# IQModulator.net
KiCad netlist of a schematic drawn in EAGLE
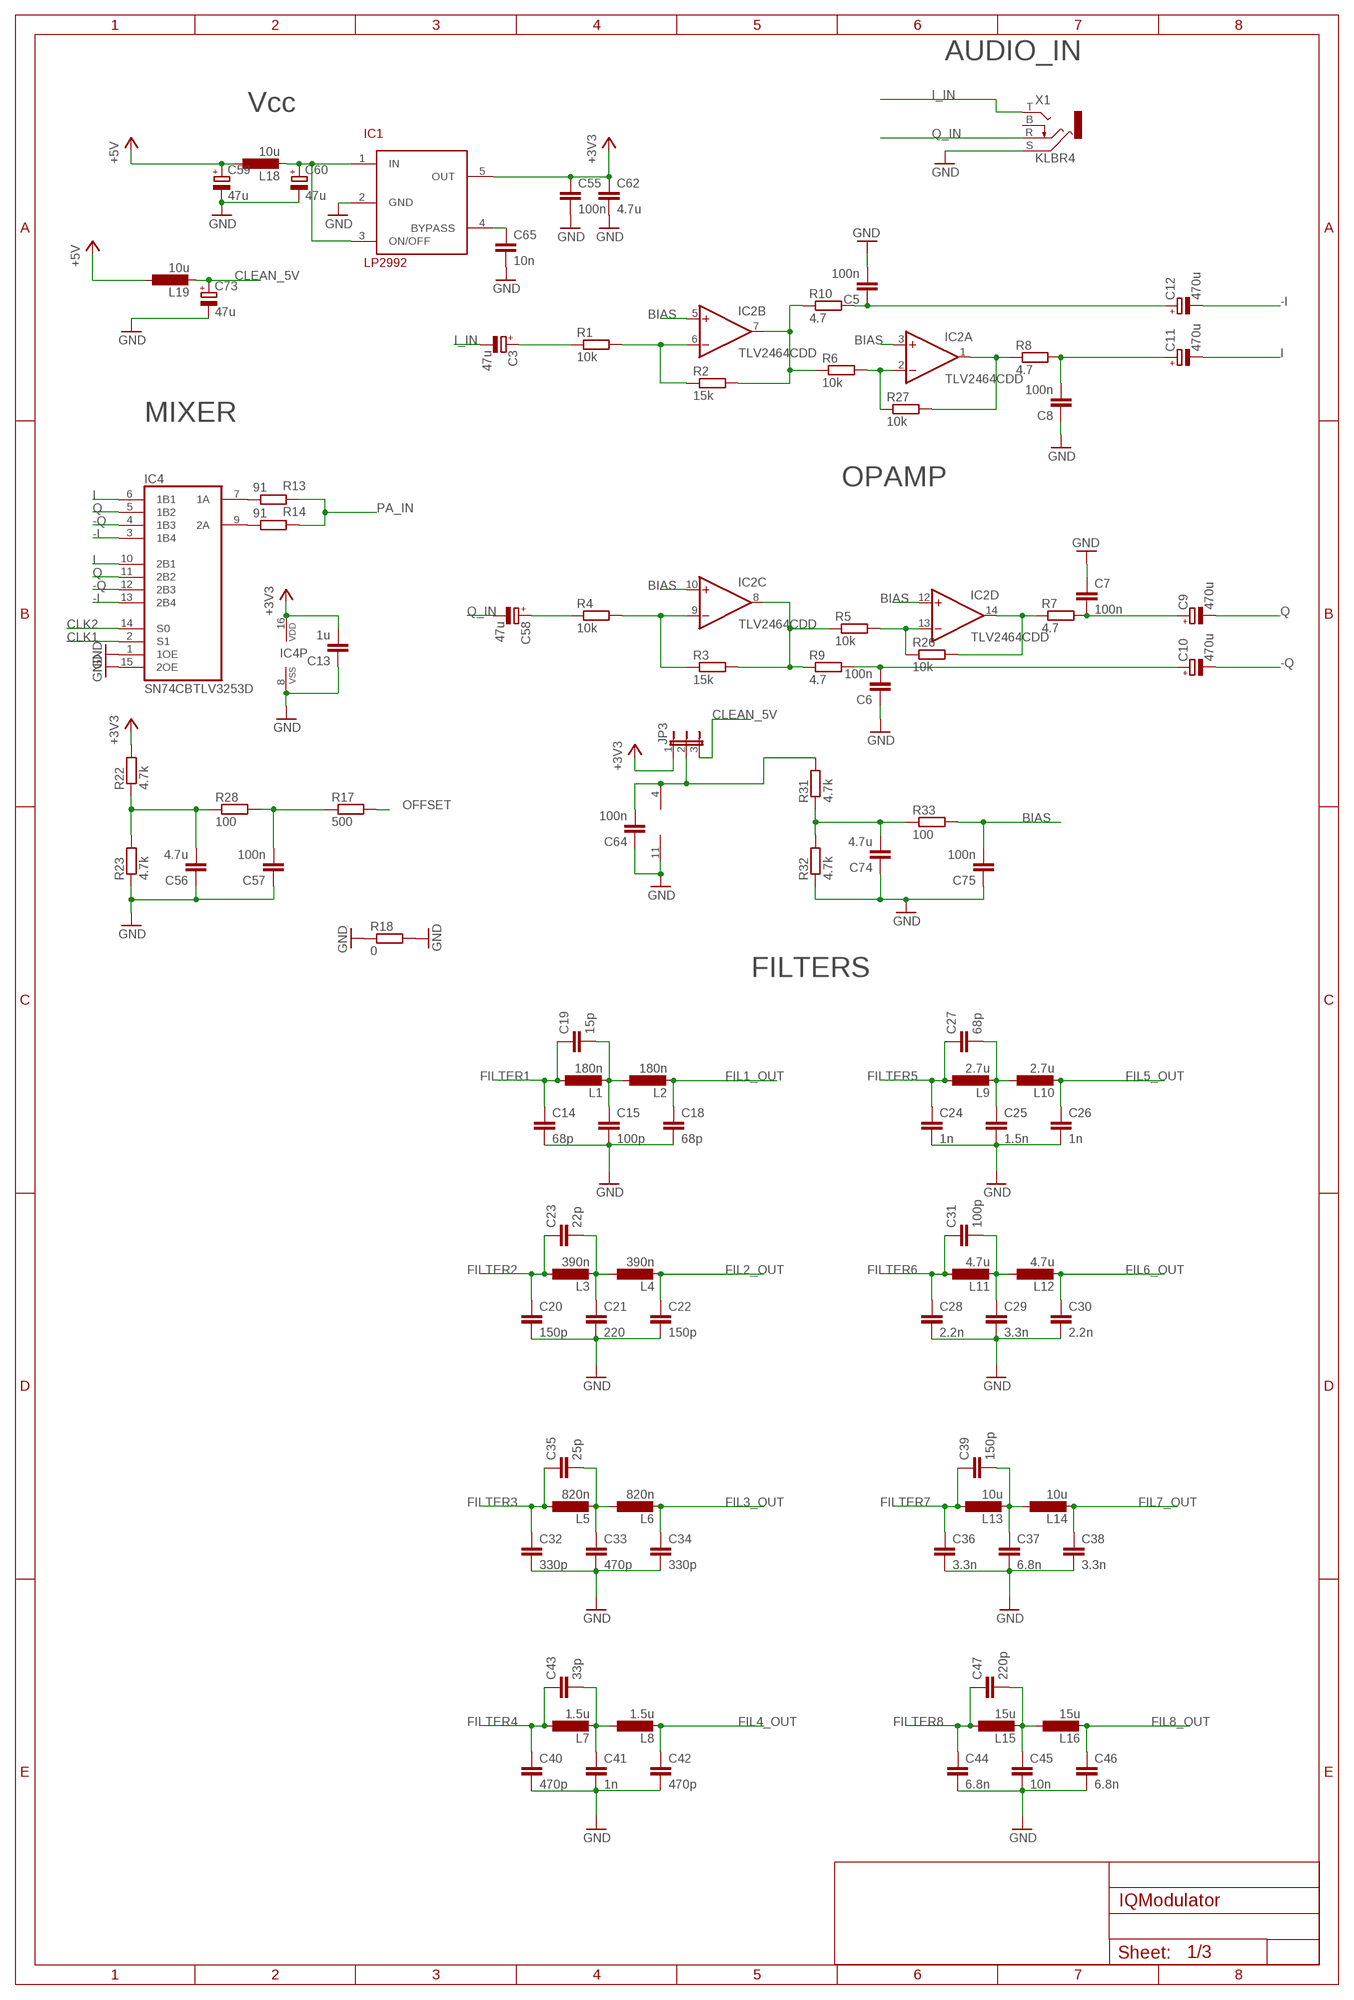
[diagram p0: schematic, sheet 1]
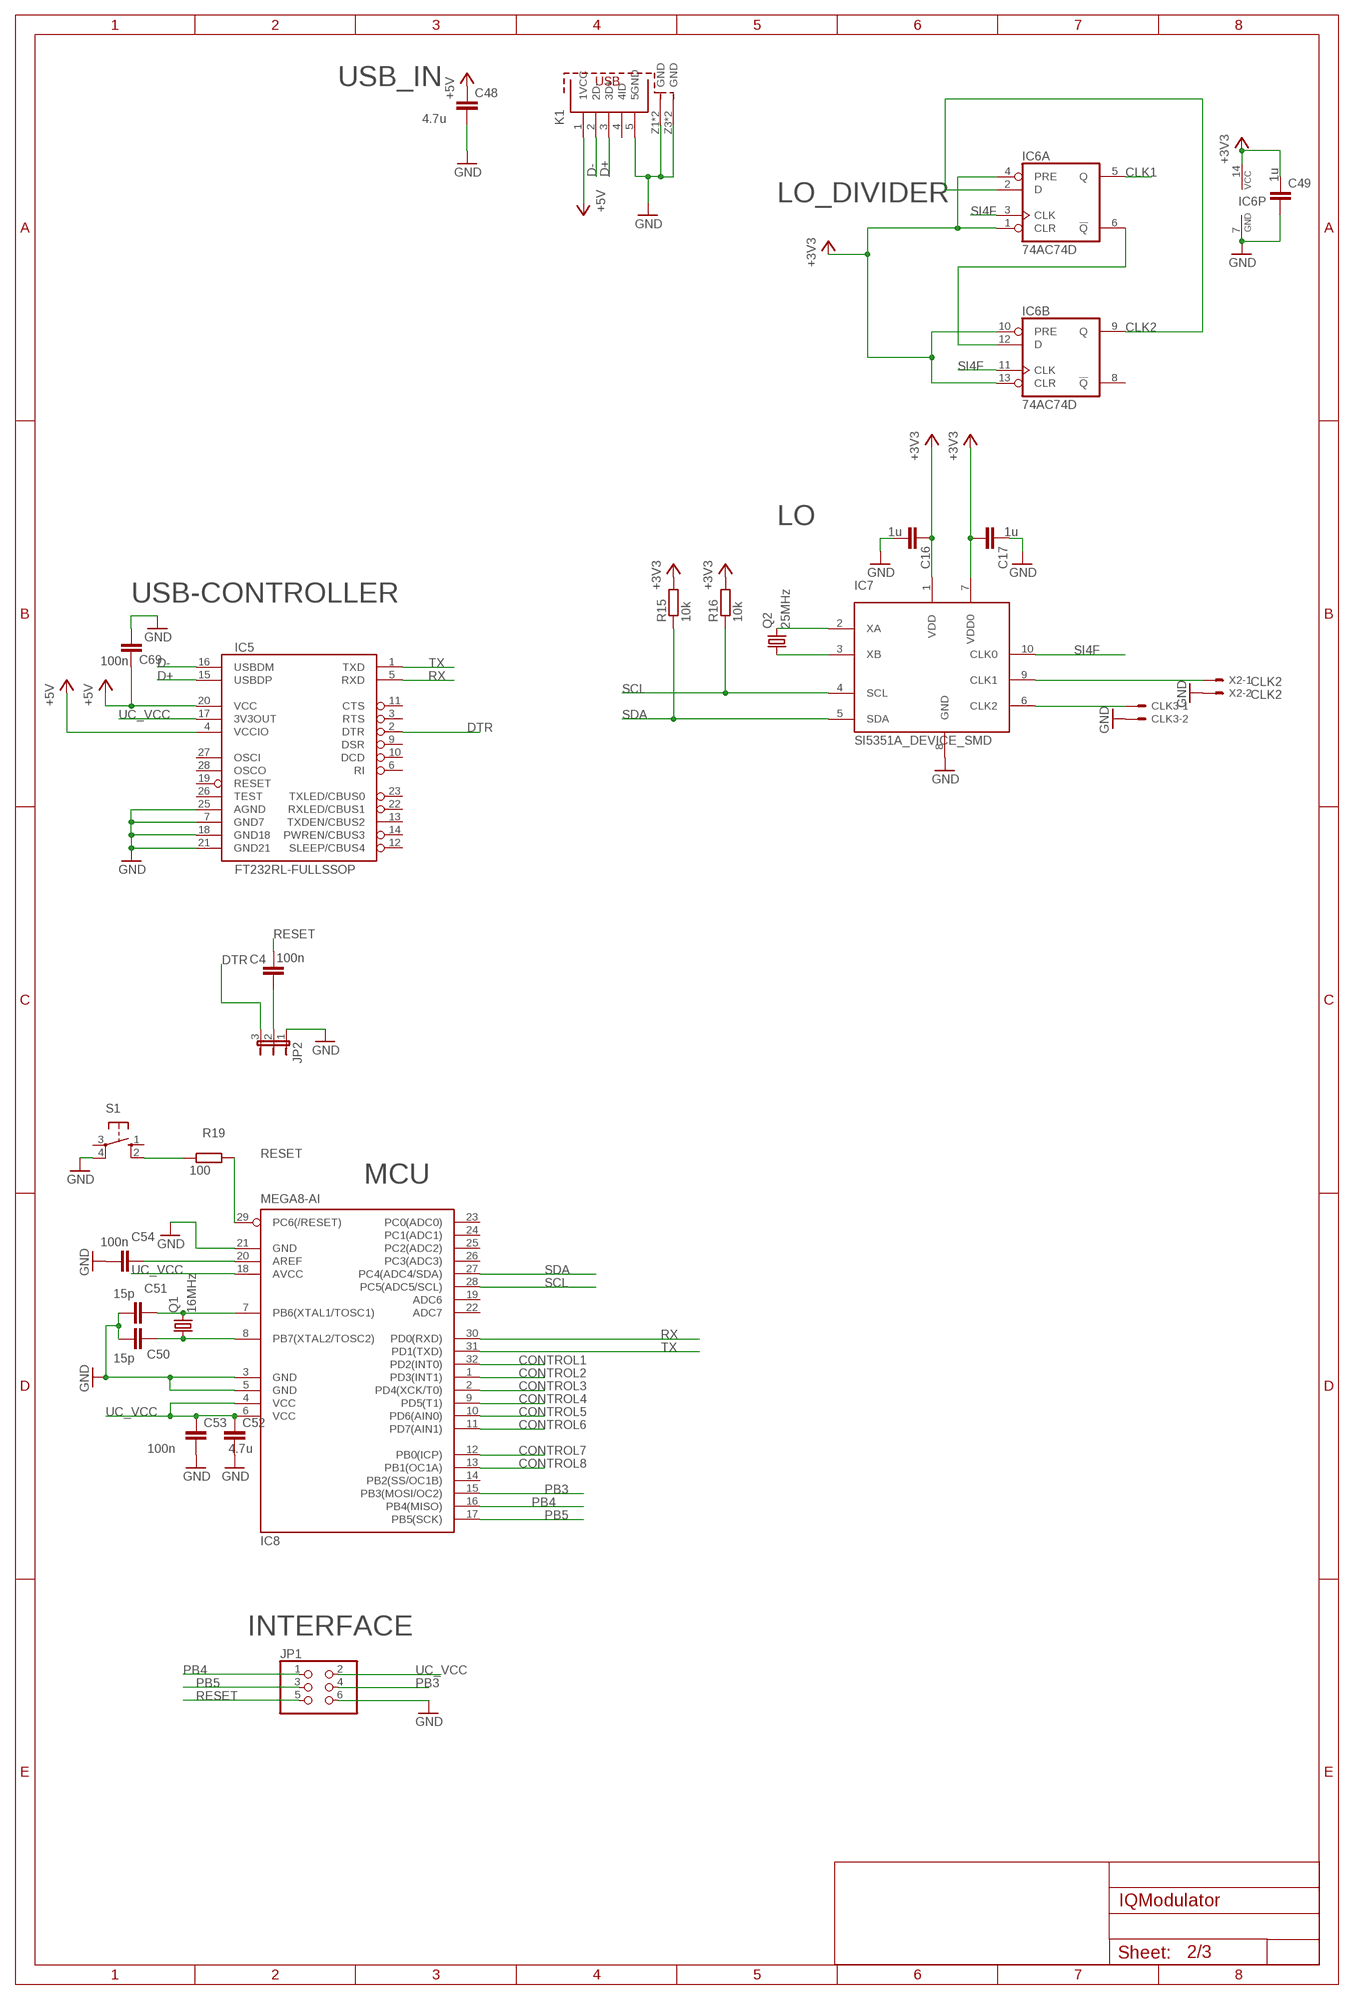
[diagram p1: schematic, sheet 2]
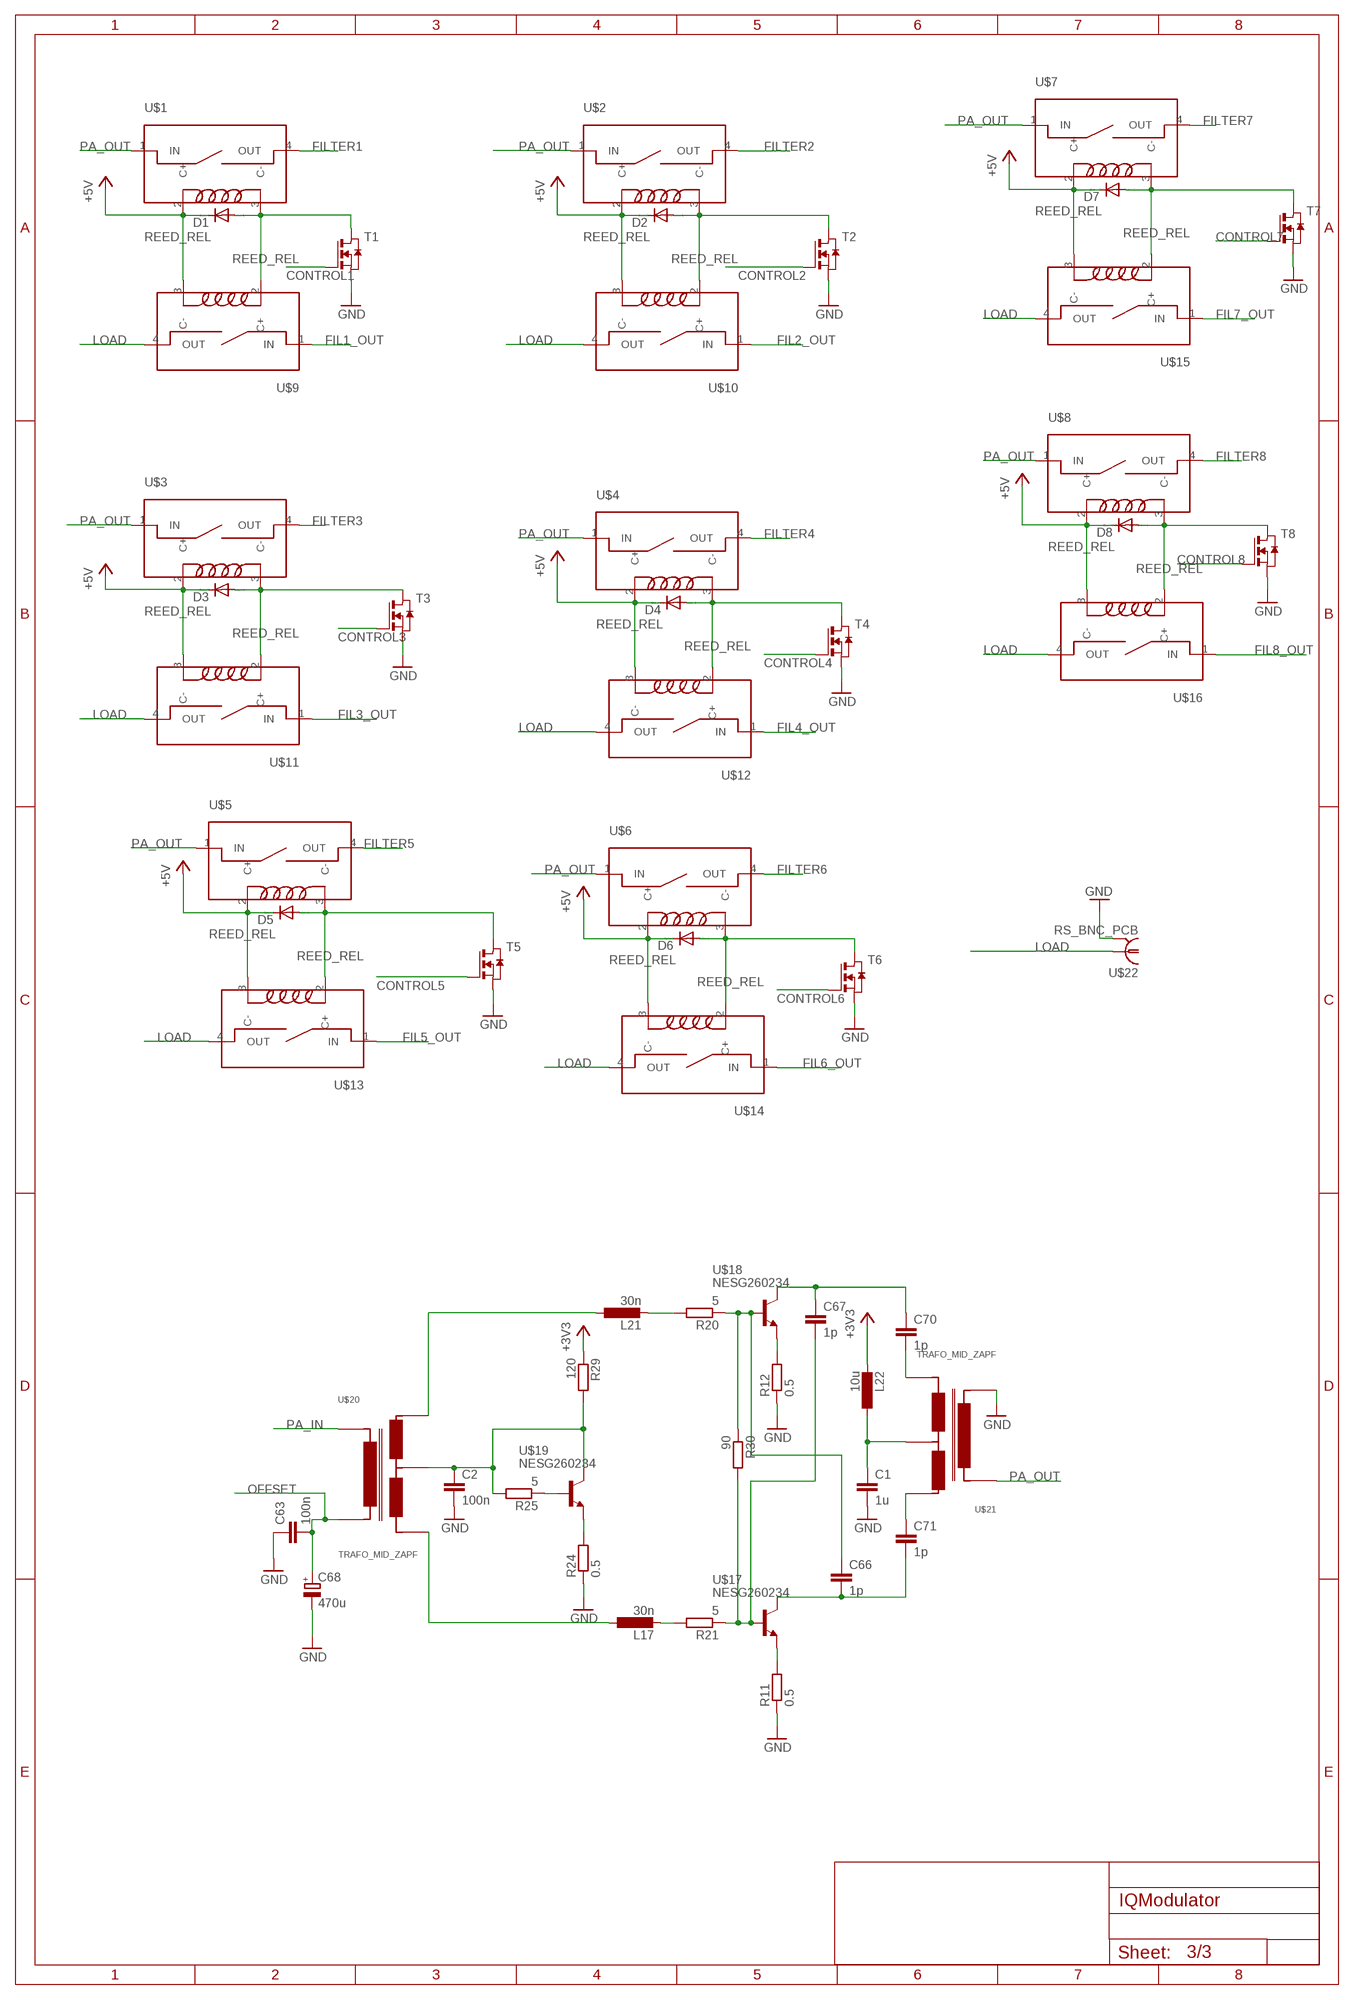
[diagram p2: schematic, sheet 3]

(export (version "E")
  (design (tool "Eeschema 10.0.6"))
  (components
    (comp (ref "C3")
      (value "47u")
      (footprint "eagle-import:PANASONIC_C")
      (libsource (lib "eagle-import") (part "CPOL-EUC"))
    )
    (comp (ref "C5")
      (value "100n")
      (footprint "eagle-import:C0805")
      (libsource (lib "eagle-import") (part "resistor_C-EUC0805"))
    )
    (comp (ref "C6")
      (value "100n")
      (footprint "eagle-import:C0805")
      (libsource (lib "eagle-import") (part "resistor_C-EUC0805"))
    )
    (comp (ref "C7")
      (value "100n")
      (footprint "eagle-import:C0805")
      (libsource (lib "eagle-import") (part "resistor_C-EUC0805"))
    )
    (comp (ref "C8")
      (value "100n")
      (footprint "eagle-import:C0805")
      (libsource (lib "eagle-import") (part "resistor_C-EUC0805"))
    )
    (comp (ref "C9")
      (value "470u")
      (footprint "eagle-import:PANASONIC_D")
      (libsource (lib "eagle-import") (part "CPOL-EUD"))
    )
    (comp (ref "C10")
      (value "470u")
      (footprint "eagle-import:PANASONIC_D")
      (libsource (lib "eagle-import") (part "CPOL-EUD"))
    )
    (comp (ref "C11")
      (value "470u")
      (footprint "eagle-import:PANASONIC_D")
      (libsource (lib "eagle-import") (part "CPOL-EUD"))
    )
    (comp (ref "C12")
      (value "470u")
      (footprint "eagle-import:PANASONIC_D")
      (libsource (lib "eagle-import") (part "CPOL-EUD"))
    )
    (comp (ref "C13")
      (value "1u")
      (footprint "eagle-import:C0805")
      (libsource (lib "eagle-import") (part "resistor_C-EUC0805"))
    )
    (comp (ref "C14")
      (value "68p")
      (footprint "eagle-import:C0805")
      (libsource (lib "eagle-import") (part "resistor_C-EUC0805"))
    )
    (comp (ref "C15")
      (value "100p")
      (footprint "eagle-import:C0805")
      (libsource (lib "eagle-import") (part "resistor_C-EUC0805"))
    )
    (comp (ref "C18")
      (value "68p")
      (footprint "eagle-import:C0805")
      (libsource (lib "eagle-import") (part "resistor_C-EUC0805"))
    )
    (comp (ref "C19")
      (value "15p")
      (footprint "eagle-import:C0805")
      (libsource (lib "eagle-import") (part "resistor_C-EUC0805"))
    )
    (comp (ref "C20")
      (value "150p")
      (footprint "eagle-import:C0805")
      (libsource (lib "eagle-import") (part "resistor_C-EUC0805"))
    )
    (comp (ref "C21")
      (value "220")
      (footprint "eagle-import:C0805")
      (libsource (lib "eagle-import") (part "resistor_C-EUC0805"))
    )
    (comp (ref "C22")
      (value "150p")
      (footprint "eagle-import:C0805")
      (libsource (lib "eagle-import") (part "resistor_C-EUC0805"))
    )
    (comp (ref "C23")
      (value "22p")
      (footprint "eagle-import:C0805")
      (libsource (lib "eagle-import") (part "resistor_C-EUC0805"))
    )
    (comp (ref "C24")
      (value "1n")
      (footprint "eagle-import:C0805")
      (libsource (lib "eagle-import") (part "resistor_C-EUC0805"))
    )
    (comp (ref "C25")
      (value "1.5n")
      (footprint "eagle-import:C0805")
      (libsource (lib "eagle-import") (part "resistor_C-EUC0805"))
    )
    (comp (ref "C26")
      (value "1n")
      (footprint "eagle-import:C0805")
      (libsource (lib "eagle-import") (part "resistor_C-EUC0805"))
    )
    (comp (ref "C27")
      (value "68p")
      (footprint "eagle-import:C0805")
      (libsource (lib "eagle-import") (part "resistor_C-EUC0805"))
    )
    (comp (ref "C28")
      (value "2.2n")
      (footprint "eagle-import:C0805")
      (libsource (lib "eagle-import") (part "resistor_C-EUC0805"))
    )
    (comp (ref "C29")
      (value "3.3n")
      (footprint "eagle-import:C0805")
      (libsource (lib "eagle-import") (part "resistor_C-EUC0805"))
    )
    (comp (ref "C30")
      (value "2.2n")
      (footprint "eagle-import:C0805")
      (libsource (lib "eagle-import") (part "resistor_C-EUC0805"))
    )
    (comp (ref "C31")
      (value "100p")
      (footprint "eagle-import:C0805")
      (libsource (lib "eagle-import") (part "resistor_C-EUC0805"))
    )
    (comp (ref "C32")
      (value "330p")
      (footprint "eagle-import:C0805")
      (libsource (lib "eagle-import") (part "resistor_C-EUC0805"))
    )
    (comp (ref "C33")
      (value "470p")
      (footprint "eagle-import:C0805")
      (libsource (lib "eagle-import") (part "resistor_C-EUC0805"))
    )
    (comp (ref "C34")
      (value "330p")
      (footprint "eagle-import:C0805")
      (libsource (lib "eagle-import") (part "resistor_C-EUC0805"))
    )
    (comp (ref "C35")
      (value "25p")
      (footprint "eagle-import:C0805")
      (libsource (lib "eagle-import") (part "resistor_C-EUC0805"))
    )
    (comp (ref "C36")
      (value "3.3n")
      (footprint "eagle-import:C0805")
      (libsource (lib "eagle-import") (part "resistor_C-EUC0805"))
    )
    (comp (ref "C37")
      (value "6.8n")
      (footprint "eagle-import:C0805")
      (libsource (lib "eagle-import") (part "resistor_C-EUC0805"))
    )
    (comp (ref "C38")
      (value "3.3n")
      (footprint "eagle-import:C0805")
      (libsource (lib "eagle-import") (part "resistor_C-EUC0805"))
    )
    (comp (ref "C39")
      (value "150p")
      (footprint "eagle-import:C0805")
      (libsource (lib "eagle-import") (part "resistor_C-EUC0805"))
    )
    (comp (ref "C40")
      (value "470p")
      (footprint "eagle-import:C0805")
      (libsource (lib "eagle-import") (part "resistor_C-EUC0805"))
    )
    (comp (ref "C41")
      (value "1n")
      (footprint "eagle-import:C0805")
      (libsource (lib "eagle-import") (part "resistor_C-EUC0805"))
    )
    (comp (ref "C42")
      (value "470p")
      (footprint "eagle-import:C0805")
      (libsource (lib "eagle-import") (part "resistor_C-EUC0805"))
    )
    (comp (ref "C43")
      (value "33p")
      (footprint "eagle-import:C0805")
      (libsource (lib "eagle-import") (part "resistor_C-EUC0805"))
    )
    (comp (ref "C44")
      (value "6.8n")
      (footprint "eagle-import:C0805")
      (libsource (lib "eagle-import") (part "resistor_C-EUC0805"))
    )
    (comp (ref "C45")
      (value "10n")
      (footprint "eagle-import:C0805")
      (libsource (lib "eagle-import") (part "resistor_C-EUC0805"))
    )
    (comp (ref "C46")
      (value "6.8n")
      (footprint "eagle-import:C0805")
      (libsource (lib "eagle-import") (part "resistor_C-EUC0805"))
    )
    (comp (ref "C47")
      (value "220p")
      (footprint "eagle-import:C0805")
      (libsource (lib "eagle-import") (part "resistor_C-EUC0805"))
    )
    (comp (ref "C55")
      (value "100n")
      (footprint "eagle-import:C0805")
      (libsource (lib "eagle-import") (part "resistor_C-EUC0805"))
    )
    (comp (ref "C56")
      (value "4.7u")
      (footprint "eagle-import:C0805")
      (libsource (lib "eagle-import") (part "resistor_C-EUC0805"))
    )
    (comp (ref "C57")
      (value "100n")
      (footprint "eagle-import:C0805")
      (libsource (lib "eagle-import") (part "resistor_C-EUC0805"))
    )
    (comp (ref "C58")
      (value "47u")
      (footprint "eagle-import:PANASONIC_C")
      (libsource (lib "eagle-import") (part "CPOL-EUC"))
    )
    (comp (ref "C59")
      (value "47u")
      (footprint "eagle-import:PANASONIC_C")
      (libsource (lib "eagle-import") (part "CPOL-EUC"))
    )
    (comp (ref "C60")
      (value "47u")
      (footprint "eagle-import:PANASONIC_C")
      (libsource (lib "eagle-import") (part "CPOL-EUC"))
    )
    (comp (ref "C62")
      (value "4.7u")
      (footprint "eagle-import:C0805")
      (libsource (lib "eagle-import") (part "resistor_C-EUC0805"))
    )
    (comp (ref "C64")
      (value "100n")
      (footprint "eagle-import:C0805")
      (libsource (lib "eagle-import") (part "resistor_C-EUC0805"))
    )
    (comp (ref "C65")
      (value "10n")
      (footprint "eagle-import:C0805")
      (libsource (lib "eagle-import") (part "resistor_C-EUC0805"))
    )
    (comp (ref "C73")
      (value "47u")
      (footprint "eagle-import:PANASONIC_C")
      (libsource (lib "eagle-import") (part "CPOL-EUC"))
    )
    (comp (ref "C74")
      (value "4.7u")
      (footprint "eagle-import:C0805")
      (libsource (lib "eagle-import") (part "resistor_C-EUC0805"))
    )
    (comp (ref "C75")
      (value "100n")
      (footprint "eagle-import:C0805")
      (libsource (lib "eagle-import") (part "resistor_C-EUC0805"))
    )
    (comp (ref "IC1")
      (value "LP2992")
      (footprint "eagle-import:SOT-23-5")
      (libsource (lib "eagle-import") (part "LP2992"))
    )
    (comp (ref "IC2")
      (value "TLV2464CDD")
      (footprint "eagle-import:SO14")
      (libsource (lib "eagle-import") (part "TLV2464CDD"))
    )
    (comp (ref "IC4")
      (value "SN74CBTLV3253D")
      (footprint "eagle-import:SO16")
      (libsource (lib "eagle-import") (part "SN74CBTLV3253D"))
    )
    (comp (ref "JP3")
      (value "JP2E")
      (footprint "eagle-import:JP2")
      (libsource (lib "eagle-import") (part "JP2E"))
    )
    (comp (ref "L1")
      (value "180n")
      (footprint "eagle-import:L0805")
      (libsource (lib "eagle-import") (part "LL0805"))
    )
    (comp (ref "L2")
      (value "180n")
      (footprint "eagle-import:L0805")
      (libsource (lib "eagle-import") (part "LL0805"))
    )
    (comp (ref "L3")
      (value "390n")
      (footprint "eagle-import:L0805")
      (libsource (lib "eagle-import") (part "LL0805"))
    )
    (comp (ref "L4")
      (value "390n")
      (footprint "eagle-import:L0805")
      (libsource (lib "eagle-import") (part "LL0805"))
    )
    (comp (ref "L5")
      (value "820n")
      (footprint "eagle-import:L0805")
      (libsource (lib "eagle-import") (part "LL0805"))
    )
    (comp (ref "L6")
      (value "820n")
      (footprint "eagle-import:L0805")
      (libsource (lib "eagle-import") (part "LL0805"))
    )
    (comp (ref "L7")
      (value "1.5u")
      (footprint "eagle-import:L0805")
      (libsource (lib "eagle-import") (part "LL0805"))
    )
    (comp (ref "L8")
      (value "1.5u")
      (footprint "eagle-import:L0805")
      (libsource (lib "eagle-import") (part "LL0805"))
    )
    (comp (ref "L9")
      (value "2.7u")
      (footprint "eagle-import:L0805")
      (libsource (lib "eagle-import") (part "LL0805"))
    )
    (comp (ref "L10")
      (value "2.7u")
      (footprint "eagle-import:L0805")
      (libsource (lib "eagle-import") (part "LL0805"))
    )
    (comp (ref "L11")
      (value "4.7u")
      (footprint "eagle-import:L0805")
      (libsource (lib "eagle-import") (part "LL0805"))
    )
    (comp (ref "L12")
      (value "4.7u")
      (footprint "eagle-import:L0805")
      (libsource (lib "eagle-import") (part "LL0805"))
    )
    (comp (ref "L13")
      (value "10u")
      (footprint "eagle-import:L0805")
      (libsource (lib "eagle-import") (part "LL0805"))
    )
    (comp (ref "L14")
      (value "10u")
      (footprint "eagle-import:L0805")
      (libsource (lib "eagle-import") (part "LL0805"))
    )
    (comp (ref "L15")
      (value "15u")
      (footprint "eagle-import:L1008")
      (libsource (lib "eagle-import") (part "L1008"))
    )
    (comp (ref "L16")
      (value "15u")
      (footprint "eagle-import:L1008")
      (libsource (lib "eagle-import") (part "L1008"))
    )
    (comp (ref "L18")
      (value "10u")
      (footprint "eagle-import:L1008")
      (libsource (lib "eagle-import") (part "L1008"))
    )
    (comp (ref "L19")
      (value "10u")
      (footprint "eagle-import:L1008")
      (libsource (lib "eagle-import") (part "L1008"))
    )
    (comp (ref "R1")
      (value "10k")
      (footprint "eagle-import:R0805")
      (libsource (lib "eagle-import") (part "resistor_R-EU_R0805"))
    )
    (comp (ref "R2")
      (value "15k")
      (footprint "eagle-import:R0805")
      (libsource (lib "eagle-import") (part "resistor_R-EU_R0805"))
    )
    (comp (ref "R3")
      (value "15k")
      (footprint "eagle-import:R0805")
      (libsource (lib "eagle-import") (part "resistor_R-EU_R0805"))
    )
    (comp (ref "R4")
      (value "10k")
      (footprint "eagle-import:R0805")
      (libsource (lib "eagle-import") (part "resistor_R-EU_R0805"))
    )
    (comp (ref "R5")
      (value "10k")
      (footprint "eagle-import:R0805")
      (libsource (lib "eagle-import") (part "resistor_R-EU_R0805"))
    )
    (comp (ref "R6")
      (value "10k")
      (footprint "eagle-import:R0805")
      (libsource (lib "eagle-import") (part "resistor_R-EU_R0805"))
    )
    (comp (ref "R7")
      (value "4.7")
      (footprint "eagle-import:R0805")
      (libsource (lib "eagle-import") (part "resistor_R-EU_R0805"))
    )
    (comp (ref "R8")
      (value "4.7")
      (footprint "eagle-import:R0805")
      (libsource (lib "eagle-import") (part "resistor_R-EU_R0805"))
    )
    (comp (ref "R9")
      (value "4.7")
      (footprint "eagle-import:R0805")
      (libsource (lib "eagle-import") (part "resistor_R-EU_R0805"))
    )
    (comp (ref "R10")
      (value "4.7")
      (footprint "eagle-import:R0805")
      (libsource (lib "eagle-import") (part "resistor_R-EU_R0805"))
    )
    (comp (ref "R13")
      (value "91")
      (footprint "eagle-import:R0805")
      (libsource (lib "eagle-import") (part "resistor_R-EU_R0805"))
    )
    (comp (ref "R14")
      (value "91")
      (footprint "eagle-import:R0805")
      (libsource (lib "eagle-import") (part "resistor_R-EU_R0805"))
    )
    (comp (ref "R17")
      (value "500")
      (footprint "eagle-import:R0805")
      (libsource (lib "eagle-import") (part "resistor_R-EU_R0805"))
    )
    (comp (ref "R18")
      (value "0")
      (footprint "eagle-import:R0805")
      (libsource (lib "eagle-import") (part "resistor_R-EU_R0805"))
    )
    (comp (ref "R22")
      (value "4.7k")
      (footprint "eagle-import:R0805")
      (libsource (lib "eagle-import") (part "resistor_R-EU_R0805"))
    )
    (comp (ref "R23")
      (value "4.7k")
      (footprint "eagle-import:R0805")
      (libsource (lib "eagle-import") (part "resistor_R-EU_R0805"))
    )
    (comp (ref "R26")
      (value "10k")
      (footprint "eagle-import:R0805")
      (libsource (lib "eagle-import") (part "resistor_R-EU_R0805"))
    )
    (comp (ref "R27")
      (value "10k")
      (footprint "eagle-import:R0805")
      (libsource (lib "eagle-import") (part "resistor_R-EU_R0805"))
    )
    (comp (ref "R28")
      (value "100")
      (footprint "eagle-import:R0805")
      (libsource (lib "eagle-import") (part "resistor_R-EU_R0805"))
    )
    (comp (ref "R31")
      (value "4.7k")
      (footprint "eagle-import:R0805")
      (libsource (lib "eagle-import") (part "resistor_R-EU_R0805"))
    )
    (comp (ref "R32")
      (value "4.7k")
      (footprint "eagle-import:R0805")
      (libsource (lib "eagle-import") (part "resistor_R-EU_R0805"))
    )
    (comp (ref "R33")
      (value "100")
      (footprint "eagle-import:R0805")
      (libsource (lib "eagle-import") (part "resistor_R-EU_R0805"))
    )
    (comp (ref "X1")
      (value "KLBR4")
      (footprint "eagle-import:KLBR4")
      (fields (field (name "MPN") "KLBR 4"))
      (libsource (lib "eagle-import") (part "KLBR4"))
    )
    (comp (ref "C4")
      (value "100n")
      (footprint "eagle-import:C0805")
      (libsource (lib "eagle-import") (part "resistor_C-EUC0805"))
    )
    (comp (ref "C16")
      (value "1u")
      (footprint "eagle-import:C0805")
      (libsource (lib "eagle-import") (part "resistor_C-EUC0805"))
    )
    (comp (ref "C17")
      (value "1u")
      (footprint "eagle-import:C0805")
      (libsource (lib "eagle-import") (part "resistor_C-EUC0805"))
    )
    (comp (ref "C48")
      (value "4.7u")
      (footprint "eagle-import:C0805")
      (libsource (lib "eagle-import") (part "resistor_C-EUC0805"))
    )
    (comp (ref "C49")
      (value "1u")
      (footprint "eagle-import:C0805")
      (libsource (lib "eagle-import") (part "resistor_C-EUC0805"))
    )
    (comp (ref "C50")
      (value "15p")
      (footprint "eagle-import:C0805")
      (libsource (lib "eagle-import") (part "resistor_C-EUC0805"))
    )
    (comp (ref "C51")
      (value "15p")
      (footprint "eagle-import:C0805")
      (libsource (lib "eagle-import") (part "resistor_C-EUC0805"))
    )
    (comp (ref "C52")
      (value "4.7u")
      (footprint "eagle-import:C0805")
      (libsource (lib "eagle-import") (part "resistor_C-EUC0805"))
    )
    (comp (ref "C53")
      (value "100n")
      (footprint "eagle-import:C0805")
      (libsource (lib "eagle-import") (part "resistor_C-EUC0805"))
    )
    (comp (ref "C54")
      (value "100n")
      (footprint "eagle-import:C0805")
      (libsource (lib "eagle-import") (part "resistor_C-EUC0805"))
    )
    (comp (ref "C69")
      (value "100n")
      (footprint "eagle-import:C0805")
      (libsource (lib "eagle-import") (part "resistor_C-EUC0805"))
    )
    (comp (ref "CLK3")
      (value "KK-156-2")
      (footprint "eagle-import:KK-156-2")
      (libsource (lib "eagle-import") (part "KK-156-2"))
    )
    (comp (ref "IC5")
      (value "FT232RL-FULLSSOP")
      (footprint "eagle-import:SSOP28DB")
      (libsource (lib "eagle-import") (part "FT232RL-FULLSSOP"))
    )
    (comp (ref "IC6")
      (value "74AC74D")
      (footprint "eagle-import:SO14")
      (libsource (lib "eagle-import") (part "7474DAC"))
    )
    (comp (ref "IC7")
      (value "SI5351A_DEVICE_SMD")
      (footprint "eagle-import:10-MSOP")
      (libsource (lib "eagle-import") (part "SI5351A_DEVICE_SMD"))
    )
    (comp (ref "IC8")
      (value "MEGA8-AI")
      (footprint "eagle-import:TQFP32-08")
      (fields (field (name "MPN") "ATMEGA8-16AU"))
      (libsource (lib "eagle-import") (part "MEGA8-AI"))
    )
    (comp (ref "JP1")
      (value "HEADER-2X3")
      (footprint "eagle-import:2X03_ROUND_70MIL")
      (libsource (lib "eagle-import") (part "HEADER-2X3"))
    )
    (comp (ref "JP2")
      (value "JP2E")
      (footprint "eagle-import:JP2")
      (libsource (lib "eagle-import") (part "JP2E"))
    )
    (comp (ref "K1")
      (value "629105150521")
      (footprint "eagle-import:629105150521")
      (libsource (lib "eagle-import") (part "629105150521"))
    )
    (comp (ref "Q1")
      (value "16MHz")
      (footprint "eagle-import:HC49_S")
      (libsource (lib "eagle-import") (part "CRYSTALHC49S"))
    )
    (comp (ref "Q2")
      (value "25MHz")
      (footprint "eagle-import:HC49_S")
      (libsource (lib "eagle-import") (part "CRYSTALHC49S"))
    )
    (comp (ref "R15")
      (value "10k")
      (footprint "eagle-import:R0805")
      (libsource (lib "eagle-import") (part "resistor_R-EU_R0805"))
    )
    (comp (ref "R16")
      (value "10k")
      (footprint "eagle-import:R0805")
      (libsource (lib "eagle-import") (part "resistor_R-EU_R0805"))
    )
    (comp (ref "R19")
      (value "100")
      (footprint "eagle-import:R0805")
      (libsource (lib "eagle-import") (part "resistor_R-EU_R0805"))
    )
    (comp (ref "S1")
      (value "10-XX")
      (footprint "eagle-import:B3F-10XX")
      (fields (field (name "MPN") "B3F-1000"))
      (libsource (lib "eagle-import") (part "10-XX"))
    )
    (comp (ref "X2")
      (value "CLK2")
      (footprint "eagle-import:KK-156-2")
      (libsource (lib "eagle-import") (part "KK-156-2"))
    )
    (comp (ref "C1")
      (value "1u")
      (footprint "eagle-import:C0805")
      (libsource (lib "eagle-import") (part "C-EUC0805"))
    )
    (comp (ref "C2")
      (value "100n")
      (footprint "eagle-import:C0805")
      (libsource (lib "eagle-import") (part "C-EUC0805"))
    )
    (comp (ref "C63")
      (value "100n")
      (footprint "eagle-import:C0805")
      (libsource (lib "eagle-import") (part "C-EUC0805"))
    )
    (comp (ref "C66")
      (value "1p")
      (footprint "eagle-import:C0805")
      (libsource (lib "eagle-import") (part "C-EUC0805"))
    )
    (comp (ref "C67")
      (value "1p")
      (footprint "eagle-import:C0805")
      (libsource (lib "eagle-import") (part "C-EUC0805"))
    )
    (comp (ref "C68")
      (value "470u")
      (footprint "eagle-import:PANASONIC_D")
      (libsource (lib "eagle-import") (part "CPOL-EUD"))
    )
    (comp (ref "C70")
      (value "1p")
      (footprint "eagle-import:C0805")
      (libsource (lib "eagle-import") (part "C-EUC0805"))
    )
    (comp (ref "C71")
      (value "1p")
      (footprint "eagle-import:C0805")
      (libsource (lib "eagle-import") (part "C-EUC0805"))
    )
    (comp (ref "D1")
      (value "DIODE-DO214AA")
      (footprint "eagle-import:DO214AA")
      (libsource (lib "eagle-import") (part "DIODE-DO214AA"))
    )
    (comp (ref "D2")
      (value "DIODE-DO214AA")
      (footprint "eagle-import:DO214AA")
      (libsource (lib "eagle-import") (part "DIODE-DO214AA"))
    )
    (comp (ref "D3")
      (value "DIODE-DO214AA")
      (footprint "eagle-import:DO214AA")
      (libsource (lib "eagle-import") (part "DIODE-DO214AA"))
    )
    (comp (ref "D4")
      (value "DIODE-DO214AA")
      (footprint "eagle-import:DO214AA")
      (libsource (lib "eagle-import") (part "DIODE-DO214AA"))
    )
    (comp (ref "D5")
      (value "DIODE-DO214AA")
      (footprint "eagle-import:DO214AA")
      (libsource (lib "eagle-import") (part "DIODE-DO214AA"))
    )
    (comp (ref "D6")
      (value "DIODE-DO214AA")
      (footprint "eagle-import:DO214AA")
      (libsource (lib "eagle-import") (part "DIODE-DO214AA"))
    )
    (comp (ref "D7")
      (value "DIODE-DO214AA")
      (footprint "eagle-import:DO214AA")
      (libsource (lib "eagle-import") (part "DIODE-DO214AA"))
    )
    (comp (ref "D8")
      (value "DIODE-DO214AA")
      (footprint "eagle-import:DO214AA")
      (libsource (lib "eagle-import") (part "DIODE-DO214AA"))
    )
    (comp (ref "L17")
      (value "30n")
      (footprint "eagle-import:L0805")
      (libsource (lib "eagle-import") (part "LL0805"))
    )
    (comp (ref "L21")
      (value "30n")
      (footprint "eagle-import:L0805")
      (libsource (lib "eagle-import") (part "LL0805"))
    )
    (comp (ref "L22")
      (value "10u")
      (footprint "eagle-import:L0805")
      (libsource (lib "eagle-import") (part "LL0805"))
    )
    (comp (ref "R11")
      (value "0.5")
      (footprint "eagle-import:R0805")
      (libsource (lib "eagle-import") (part "R-EU_R0805"))
    )
    (comp (ref "R12")
      (value "0.5")
      (footprint "eagle-import:R0805")
      (libsource (lib "eagle-import") (part "R-EU_R0805"))
    )
    (comp (ref "R20")
      (value "5")
      (footprint "eagle-import:R0805")
      (libsource (lib "eagle-import") (part "R-EU_R0805"))
    )
    (comp (ref "R21")
      (value "5")
      (footprint "eagle-import:R0805")
      (libsource (lib "eagle-import") (part "R-EU_R0805"))
    )
    (comp (ref "R24")
      (value "0.5")
      (footprint "eagle-import:R0805")
      (libsource (lib "eagle-import") (part "R-EU_R0805"))
    )
    (comp (ref "R25")
      (value "5")
      (footprint "eagle-import:R0805")
      (libsource (lib "eagle-import") (part "R-EU_R0805"))
    )
    (comp (ref "R29")
      (value "120")
      (footprint "eagle-import:R0805")
      (libsource (lib "eagle-import") (part "R-EU_R0805"))
    )
    (comp (ref "R30")
      (value "90")
      (footprint "eagle-import:R0805")
      (libsource (lib "eagle-import") (part "R-EU_R0805"))
    )
    (comp (ref "T1")
      (value "NMOSSOT23")
      (footprint "eagle-import:SOT-23")
      (libsource (lib "eagle-import") (part "NMOSSOT23"))
    )
    (comp (ref "T2")
      (value "NMOSSOT23")
      (footprint "eagle-import:SOT-23")
      (libsource (lib "eagle-import") (part "NMOSSOT23"))
    )
    (comp (ref "T3")
      (value "NMOSSOT23")
      (footprint "eagle-import:SOT-23")
      (libsource (lib "eagle-import") (part "NMOSSOT23"))
    )
    (comp (ref "T4")
      (value "NMOSSOT23")
      (footprint "eagle-import:SOT-23")
      (libsource (lib "eagle-import") (part "NMOSSOT23"))
    )
    (comp (ref "T5")
      (value "NMOSSOT23")
      (footprint "eagle-import:SOT-23")
      (libsource (lib "eagle-import") (part "NMOSSOT23"))
    )
    (comp (ref "T6")
      (value "NMOSSOT23")
      (footprint "eagle-import:SOT-23")
      (libsource (lib "eagle-import") (part "NMOSSOT23"))
    )
    (comp (ref "T7")
      (value "NMOSSOT23")
      (footprint "eagle-import:SOT-23")
      (libsource (lib "eagle-import") (part "NMOSSOT23"))
    )
    (comp (ref "T8")
      (value "NMOSSOT23")
      (footprint "eagle-import:SOT-23")
      (libsource (lib "eagle-import") (part "NMOSSOT23"))
    )
    (comp (ref "U$1")
      (value "REED_REL")
      (footprint "eagle-import:REED_RELAY")
      (libsource (lib "eagle-import") (part "REED_REL"))
    )
    (comp (ref "U$2")
      (value "REED_REL")
      (footprint "eagle-import:REED_RELAY")
      (libsource (lib "eagle-import") (part "REED_REL"))
    )
    (comp (ref "U$3")
      (value "REED_REL")
      (footprint "eagle-import:REED_RELAY")
      (libsource (lib "eagle-import") (part "REED_REL"))
    )
    (comp (ref "U$4")
      (value "REED_REL")
      (footprint "eagle-import:REED_RELAY")
      (libsource (lib "eagle-import") (part "REED_REL"))
    )
    (comp (ref "U$5")
      (value "REED_REL")
      (footprint "eagle-import:REED_RELAY")
      (libsource (lib "eagle-import") (part "REED_REL"))
    )
    (comp (ref "U$6")
      (value "REED_REL")
      (footprint "eagle-import:REED_RELAY")
      (libsource (lib "eagle-import") (part "REED_REL"))
    )
    (comp (ref "U$7")
      (value "REED_REL")
      (footprint "eagle-import:REED_RELAY")
      (libsource (lib "eagle-import") (part "REED_REL"))
    )
    (comp (ref "U$8")
      (value "REED_REL")
      (footprint "eagle-import:REED_RELAY")
      (libsource (lib "eagle-import") (part "REED_REL"))
    )
    (comp (ref "U$9")
      (value "REED_REL")
      (footprint "eagle-import:REED_RELAY")
      (libsource (lib "eagle-import") (part "REED_REL"))
    )
    (comp (ref "U$10")
      (value "REED_REL")
      (footprint "eagle-import:REED_RELAY")
      (libsource (lib "eagle-import") (part "REED_REL"))
    )
    (comp (ref "U$11")
      (value "REED_REL")
      (footprint "eagle-import:REED_RELAY")
      (libsource (lib "eagle-import") (part "REED_REL"))
    )
    (comp (ref "U$12")
      (value "REED_REL")
      (footprint "eagle-import:REED_RELAY")
      (libsource (lib "eagle-import") (part "REED_REL"))
    )
    (comp (ref "U$13")
      (value "REED_REL")
      (footprint "eagle-import:REED_RELAY")
      (libsource (lib "eagle-import") (part "REED_REL"))
    )
    (comp (ref "U$14")
      (value "REED_REL")
      (footprint "eagle-import:REED_RELAY")
      (libsource (lib "eagle-import") (part "REED_REL"))
    )
    (comp (ref "U$15")
      (value "REED_REL")
      (footprint "eagle-import:REED_RELAY")
      (libsource (lib "eagle-import") (part "REED_REL"))
    )
    (comp (ref "U$16")
      (value "REED_REL")
      (footprint "eagle-import:REED_RELAY")
      (libsource (lib "eagle-import") (part "REED_REL"))
    )
    (comp (ref "U$17")
      (value "NESG260234")
      (footprint "eagle-import:SOT-89")
      (libsource (lib "eagle-import") (part "NESG260234"))
    )
    (comp (ref "U$18")
      (value "NESG260234")
      (footprint "eagle-import:SOT-89")
      (libsource (lib "eagle-import") (part "NESG260234"))
    )
    (comp (ref "U$19")
      (value "NESG260234")
      (footprint "eagle-import:SOT-89")
      (libsource (lib "eagle-import") (part "NESG260234"))
    )
    (comp (ref "U$20")
      (value "TRAFO_MID_ZAPF")
      (footprint "eagle-import:TRAFO_MID_ZAPF")
      (libsource (lib "eagle-import") (part "TRAFO_MID_ZAPF"))
    )
    (comp (ref "U$21")
      (value "TRAFO_MID_ZAPF")
      (footprint "eagle-import:TRAFO_MID_ZAPF")
      (libsource (lib "eagle-import") (part "TRAFO_MID_ZAPF"))
    )
    (comp (ref "U$22")
      (value "RS_BNC_PCB")
      (footprint "eagle-import:COAX-RS")
      (libsource (lib "eagle-import") (part "RS_BNC_PCB"))
    )
  )
  (nets
    (net (code "1") (name "+3V3") (class "Default")
      (node (ref "C13") (pin "2") (pinfunction "2_2") (pintype "passive"))
      (node (ref "C16") (pin "1") (pinfunction "1_1") (pintype "passive"))
      (node (ref "C17") (pin "2") (pinfunction "2_2") (pintype "passive"))
      (node (ref "C49") (pin "1") (pinfunction "1_1") (pintype "passive"))
      (node (ref "C55") (pin "1") (pinfunction "1_1") (pintype "passive"))
      (node (ref "C62") (pin "1") (pinfunction "1_1") (pintype "passive"))
      (node (ref "IC1") (pin "5") (pinfunction "OUT_5") (pintype "bidirectional"))
      (node (ref "IC4") (pin "16") (pinfunction "VDD_16") (pintype "power_in"))
      (node (ref "IC6") (pin "1") (pinfunction "CLR_1") (pintype "input"))
      (node (ref "IC6") (pin "10") (pinfunction "PRE_10") (pintype "input"))
      (node (ref "IC6") (pin "13") (pinfunction "CLR_13") (pintype "input"))
      (node (ref "IC6") (pin "14") (pinfunction "VCC_14") (pintype "power_in"))
      (node (ref "IC6") (pin "4") (pinfunction "PRE_4") (pintype "input"))
      (node (ref "IC7") (pin "1") (pinfunction "VDD_1") (pintype "power_in"))
      (node (ref "IC7") (pin "7") (pinfunction "VDD0_7") (pintype "power_in"))
      (node (ref "JP3") (pin "1") (pinfunction "1_1") (pintype "passive"))
      (node (ref "L22") (pin "P$2") (pinfunction "2_P$2") (pintype "passive"))
      (node (ref "R15") (pin "2") (pinfunction "2_2") (pintype "passive"))
      (node (ref "R16") (pin "2") (pinfunction "2_2") (pintype "passive"))
      (node (ref "R22") (pin "2") (pinfunction "2_2") (pintype "passive"))
      (node (ref "R29") (pin "1") (pinfunction "1_1") (pintype "passive"))
    )
    (net (code "2") (name "+5V") (class "Default")
      (node (ref "C48") (pin "1") (pinfunction "1_1") (pintype "passive"))
      (node (ref "C59") (pin "+") (pinfunction "+_+") (pintype "passive"))
      (node (ref "C69") (pin "1") (pinfunction "1_1") (pintype "passive"))
      (node (ref "D1") (pin "C") (pinfunction "C_C") (pintype "passive"))
      (node (ref "D2") (pin "C") (pinfunction "C_C") (pintype "passive"))
      (node (ref "D3") (pin "C") (pinfunction "C_C") (pintype "passive"))
      (node (ref "D4") (pin "C") (pinfunction "C_C") (pintype "passive"))
      (node (ref "D5") (pin "C") (pinfunction "C_C") (pintype "passive"))
      (node (ref "D6") (pin "C") (pinfunction "C_C") (pintype "passive"))
      (node (ref "D7") (pin "C") (pinfunction "C_C") (pintype "passive"))
      (node (ref "D8") (pin "C") (pinfunction "C_C") (pintype "passive"))
      (node (ref "IC5") (pin "20") (pinfunction "VCC_20") (pintype "power_in"))
      (node (ref "IC5") (pin "4") (pinfunction "VCCIO_4") (pintype "power_in"))
      (node (ref "K1") (pin "1") (pinfunction "1VCC_1") (pintype "passive"))
      (node (ref "L18") (pin "P$1") (pinfunction "1_P$1") (pintype "passive"))
      (node (ref "L19") (pin "P$1") (pinfunction "1_P$1") (pintype "passive"))
      (node (ref "U$1") (pin "2") (pinfunction "C+_2") (pintype "bidirectional"))
      (node (ref "U$10") (pin "3") (pinfunction "C-_3") (pintype "bidirectional"))
      (node (ref "U$11") (pin "3") (pinfunction "C-_3") (pintype "bidirectional"))
      (node (ref "U$12") (pin "3") (pinfunction "C-_3") (pintype "bidirectional"))
      (node (ref "U$13") (pin "3") (pinfunction "C-_3") (pintype "bidirectional"))
      (node (ref "U$14") (pin "3") (pinfunction "C-_3") (pintype "bidirectional"))
      (node (ref "U$15") (pin "3") (pinfunction "C-_3") (pintype "bidirectional"))
      (node (ref "U$16") (pin "3") (pinfunction "C-_3") (pintype "bidirectional"))
      (node (ref "U$2") (pin "2") (pinfunction "C+_2") (pintype "bidirectional"))
      (node (ref "U$3") (pin "2") (pinfunction "C+_2") (pintype "bidirectional"))
      (node (ref "U$4") (pin "2") (pinfunction "C+_2") (pintype "bidirectional"))
      (node (ref "U$5") (pin "2") (pinfunction "C+_2") (pintype "bidirectional"))
      (node (ref "U$6") (pin "2") (pinfunction "C+_2") (pintype "bidirectional"))
      (node (ref "U$7") (pin "2") (pinfunction "C+_2") (pintype "bidirectional"))
      (node (ref "U$8") (pin "2") (pinfunction "C+_2") (pintype "bidirectional"))
      (node (ref "U$9") (pin "3") (pinfunction "C-_3") (pintype "bidirectional"))
    )
    (net (code "3") (name "-I") (class "Default")
      (node (ref "C12") (pin "-") (pinfunction "-_-") (pintype "passive"))
      (node (ref "IC4") (pin "13") (pinfunction "2B4_13") (pintype "input"))
      (node (ref "IC4") (pin "3") (pinfunction "1B4_3") (pintype "input"))
    )
    (net (code "4") (name "-Q") (class "Default")
      (node (ref "C10") (pin "-") (pinfunction "-_-") (pintype "passive"))
      (node (ref "IC4") (pin "12") (pinfunction "2B3_12") (pintype "input"))
      (node (ref "IC4") (pin "4") (pinfunction "1B3_4") (pintype "input"))
    )
    (net (code "5") (name "BIAS") (class "Default")
      (node (ref "C75") (pin "2") (pinfunction "2_2") (pintype "passive"))
      (node (ref "IC2") (pin "10") (pinfunction "+IN_10") (pintype "input"))
      (node (ref "IC2") (pin "12") (pinfunction "+IN_12") (pintype "input"))
      (node (ref "IC2") (pin "3") (pinfunction "+IN_3") (pintype "input"))
      (node (ref "IC2") (pin "5") (pinfunction "+IN_5") (pintype "input"))
      (node (ref "R33") (pin "2") (pinfunction "2_2") (pintype "passive"))
    )
    (net (code "6") (name "CLEAN_5V") (class "Default")
      (node (ref "C73") (pin "+") (pinfunction "+_+") (pintype "passive"))
      (node (ref "JP3") (pin "3") (pinfunction "3_3") (pintype "passive"))
      (node (ref "L19") (pin "P$2") (pinfunction "2_P$2") (pintype "passive"))
    )
    (net (code "7") (name "CLK1") (class "Default")
      (node (ref "IC4") (pin "2") (pinfunction "S1_2") (pintype "input"))
      (node (ref "IC6") (pin "5") (pinfunction "Q_5") (pintype "output"))
    )
    (net (code "8") (name "CLK2") (class "Default")
      (node (ref "IC4") (pin "14") (pinfunction "S0_14") (pintype "input"))
      (node (ref "IC6") (pin "2") (pinfunction "D_2") (pintype "input"))
      (node (ref "IC6") (pin "9") (pinfunction "Q_9") (pintype "output"))
    )
    (net (code "9") (name "CONTROL1") (class "Default")
      (node (ref "IC8") (pin "32") (pinfunction "PD2(INT0)_32") (pintype "bidirectional"))
      (node (ref "T1") (pin "3") (pinfunction "G_3") (pintype "passive"))
    )
    (net (code "10") (name "CONTROL2") (class "Default")
      (node (ref "IC8") (pin "1") (pinfunction "PD3(INT1)_1") (pintype "bidirectional"))
      (node (ref "T2") (pin "3") (pinfunction "G_3") (pintype "passive"))
    )
    (net (code "11") (name "CONTROL3") (class "Default")
      (node (ref "IC8") (pin "2") (pinfunction "PD4(XCK/T0)_2") (pintype "bidirectional"))
      (node (ref "T3") (pin "3") (pinfunction "G_3") (pintype "passive"))
    )
    (net (code "12") (name "CONTROL4") (class "Default")
      (node (ref "IC8") (pin "9") (pinfunction "PD5(T1)_9") (pintype "bidirectional"))
      (node (ref "T4") (pin "3") (pinfunction "G_3") (pintype "passive"))
    )
    (net (code "13") (name "CONTROL5") (class "Default")
      (node (ref "IC8") (pin "10") (pinfunction "PD6(AIN0)_10") (pintype "bidirectional"))
      (node (ref "T5") (pin "3") (pinfunction "G_3") (pintype "passive"))
    )
    (net (code "14") (name "CONTROL6") (class "Default")
      (node (ref "IC8") (pin "11") (pinfunction "PD7(AIN1)_11") (pintype "bidirectional"))
      (node (ref "T6") (pin "3") (pinfunction "G_3") (pintype "passive"))
    )
    (net (code "15") (name "CONTROL7") (class "Default")
      (node (ref "IC8") (pin "12") (pinfunction "PB0(ICP)_12") (pintype "bidirectional"))
      (node (ref "T7") (pin "3") (pinfunction "G_3") (pintype "passive"))
    )
    (net (code "16") (name "CONTROL8") (class "Default")
      (node (ref "IC8") (pin "13") (pinfunction "PB1(OC1A)_13") (pintype "bidirectional"))
      (node (ref "T8") (pin "3") (pinfunction "G_3") (pintype "passive"))
    )
    (net (code "17") (name "D+") (class "Default")
      (node (ref "IC5") (pin "15") (pinfunction "USBDP_15") (pintype "bidirectional"))
      (node (ref "K1") (pin "3") (pinfunction "3D+_3") (pintype "passive"))
    )
    (net (code "18") (name "D-") (class "Default")
      (node (ref "IC5") (pin "16") (pinfunction "USBDM_16") (pintype "bidirectional"))
      (node (ref "K1") (pin "2") (pinfunction "2D-_2") (pintype "passive"))
    )
    (net (code "19") (name "DTR") (class "Default")
      (node (ref "IC5") (pin "2") (pinfunction "DTR_2") (pintype "output"))
      (node (ref "JP2") (pin "3") (pinfunction "3_3") (pintype "passive"))
    )
    (net (code "20") (name "FIL1_OUT") (class "Default")
      (node (ref "C18") (pin "1") (pinfunction "1_1") (pintype "passive"))
      (node (ref "L2") (pin "P$2") (pinfunction "2_P$2") (pintype "passive"))
      (node (ref "U$9") (pin "1") (pinfunction "IN_1") (pintype "bidirectional"))
    )
    (net (code "21") (name "FIL2_OUT") (class "Default")
      (node (ref "C22") (pin "1") (pinfunction "1_1") (pintype "passive"))
      (node (ref "L4") (pin "P$2") (pinfunction "2_P$2") (pintype "passive"))
      (node (ref "U$10") (pin "1") (pinfunction "IN_1") (pintype "bidirectional"))
    )
    (net (code "22") (name "FIL3_OUT") (class "Default")
      (node (ref "C34") (pin "1") (pinfunction "1_1") (pintype "passive"))
      (node (ref "L6") (pin "P$2") (pinfunction "2_P$2") (pintype "passive"))
      (node (ref "U$11") (pin "1") (pinfunction "IN_1") (pintype "bidirectional"))
    )
    (net (code "23") (name "FIL4_OUT") (class "Default")
      (node (ref "C42") (pin "1") (pinfunction "1_1") (pintype "passive"))
      (node (ref "L8") (pin "P$2") (pinfunction "2_P$2") (pintype "passive"))
      (node (ref "U$12") (pin "1") (pinfunction "IN_1") (pintype "bidirectional"))
    )
    (net (code "24") (name "FIL5_OUT") (class "Default")
      (node (ref "C26") (pin "1") (pinfunction "1_1") (pintype "passive"))
      (node (ref "L10") (pin "P$2") (pinfunction "2_P$2") (pintype "passive"))
      (node (ref "U$13") (pin "1") (pinfunction "IN_1") (pintype "bidirectional"))
    )
    (net (code "25") (name "FIL6_OUT") (class "Default")
      (node (ref "C30") (pin "1") (pinfunction "1_1") (pintype "passive"))
      (node (ref "L12") (pin "P$2") (pinfunction "2_P$2") (pintype "passive"))
      (node (ref "U$14") (pin "1") (pinfunction "IN_1") (pintype "bidirectional"))
    )
    (net (code "26") (name "FIL7_OUT") (class "Default")
      (node (ref "C38") (pin "1") (pinfunction "1_1") (pintype "passive"))
      (node (ref "L14") (pin "P$2") (pinfunction "2_P$2") (pintype "passive"))
      (node (ref "U$15") (pin "1") (pinfunction "IN_1") (pintype "bidirectional"))
    )
    (net (code "27") (name "FIL8_OUT") (class "Default")
      (node (ref "C46") (pin "1") (pinfunction "1_1") (pintype "passive"))
      (node (ref "L16") (pin "P$2") (pinfunction "2_P$2") (pintype "passive"))
      (node (ref "U$16") (pin "1") (pinfunction "IN_1") (pintype "bidirectional"))
    )
    (net (code "28") (name "FILTER1") (class "Default")
      (node (ref "C14") (pin "1") (pinfunction "1_1") (pintype "passive"))
      (node (ref "C19") (pin "1") (pinfunction "1_1") (pintype "passive"))
      (node (ref "L1") (pin "P$1") (pinfunction "1_P$1") (pintype "passive"))
      (node (ref "U$1") (pin "4") (pinfunction "OUT_4") (pintype "bidirectional"))
    )
    (net (code "29") (name "FILTER2") (class "Default")
      (node (ref "C20") (pin "1") (pinfunction "1_1") (pintype "passive"))
      (node (ref "C23") (pin "1") (pinfunction "1_1") (pintype "passive"))
      (node (ref "L3") (pin "P$1") (pinfunction "1_P$1") (pintype "passive"))
      (node (ref "U$2") (pin "4") (pinfunction "OUT_4") (pintype "bidirectional"))
    )
    (net (code "30") (name "FILTER3") (class "Default")
      (node (ref "C32") (pin "1") (pinfunction "1_1") (pintype "passive"))
      (node (ref "C35") (pin "1") (pinfunction "1_1") (pintype "passive"))
      (node (ref "L5") (pin "P$1") (pinfunction "1_P$1") (pintype "passive"))
      (node (ref "U$3") (pin "4") (pinfunction "OUT_4") (pintype "bidirectional"))
    )
    (net (code "31") (name "FILTER4") (class "Default")
      (node (ref "C40") (pin "1") (pinfunction "1_1") (pintype "passive"))
      (node (ref "C43") (pin "1") (pinfunction "1_1") (pintype "passive"))
      (node (ref "L7") (pin "P$1") (pinfunction "1_P$1") (pintype "passive"))
      (node (ref "U$4") (pin "4") (pinfunction "OUT_4") (pintype "bidirectional"))
    )
    (net (code "32") (name "FILTER5") (class "Default")
      (node (ref "C24") (pin "1") (pinfunction "1_1") (pintype "passive"))
      (node (ref "C27") (pin "1") (pinfunction "1_1") (pintype "passive"))
      (node (ref "L9") (pin "P$1") (pinfunction "1_P$1") (pintype "passive"))
      (node (ref "U$5") (pin "4") (pinfunction "OUT_4") (pintype "bidirectional"))
    )
    (net (code "33") (name "FILTER6") (class "Default")
      (node (ref "C28") (pin "1") (pinfunction "1_1") (pintype "passive"))
      (node (ref "C31") (pin "1") (pinfunction "1_1") (pintype "passive"))
      (node (ref "L11") (pin "P$1") (pinfunction "1_P$1") (pintype "passive"))
      (node (ref "U$6") (pin "4") (pinfunction "OUT_4") (pintype "bidirectional"))
    )
    (net (code "34") (name "FILTER7") (class "Default")
      (node (ref "C36") (pin "1") (pinfunction "1_1") (pintype "passive"))
      (node (ref "C39") (pin "1") (pinfunction "1_1") (pintype "passive"))
      (node (ref "L13") (pin "P$1") (pinfunction "1_P$1") (pintype "passive"))
      (node (ref "U$7") (pin "4") (pinfunction "OUT_4") (pintype "bidirectional"))
    )
    (net (code "35") (name "FILTER8") (class "Default")
      (node (ref "C44") (pin "1") (pinfunction "1_1") (pintype "passive"))
      (node (ref "C47") (pin "1") (pinfunction "1_1") (pintype "passive"))
      (node (ref "L15") (pin "P$1") (pinfunction "1_P$1") (pintype "passive"))
      (node (ref "U$8") (pin "4") (pinfunction "OUT_4") (pintype "bidirectional"))
    )
    (net (code "36") (name "GND") (class "Default")
      (node (ref "C1") (pin "2") (pinfunction "2_2") (pintype "passive"))
      (node (ref "C13") (pin "1") (pinfunction "1_1") (pintype "passive"))
      (node (ref "C14") (pin "2") (pinfunction "2_2") (pintype "passive"))
      (node (ref "C15") (pin "2") (pinfunction "2_2") (pintype "passive"))
      (node (ref "C16") (pin "2") (pinfunction "2_2") (pintype "passive"))
      (node (ref "C17") (pin "1") (pinfunction "1_1") (pintype "passive"))
      (node (ref "C18") (pin "2") (pinfunction "2_2") (pintype "passive"))
      (node (ref "C2") (pin "2") (pinfunction "2_2") (pintype "passive"))
      (node (ref "C20") (pin "2") (pinfunction "2_2") (pintype "passive"))
      (node (ref "C21") (pin "2") (pinfunction "2_2") (pintype "passive"))
      (node (ref "C22") (pin "2") (pinfunction "2_2") (pintype "passive"))
      (node (ref "C24") (pin "2") (pinfunction "2_2") (pintype "passive"))
      (node (ref "C25") (pin "2") (pinfunction "2_2") (pintype "passive"))
      (node (ref "C26") (pin "2") (pinfunction "2_2") (pintype "passive"))
      (node (ref "C28") (pin "2") (pinfunction "2_2") (pintype "passive"))
      (node (ref "C29") (pin "2") (pinfunction "2_2") (pintype "passive"))
      (node (ref "C30") (pin "2") (pinfunction "2_2") (pintype "passive"))
      (node (ref "C32") (pin "2") (pinfunction "2_2") (pintype "passive"))
      (node (ref "C33") (pin "2") (pinfunction "2_2") (pintype "passive"))
      (node (ref "C34") (pin "2") (pinfunction "2_2") (pintype "passive"))
      (node (ref "C36") (pin "2") (pinfunction "2_2") (pintype "passive"))
      (node (ref "C37") (pin "2") (pinfunction "2_2") (pintype "passive"))
      (node (ref "C38") (pin "2") (pinfunction "2_2") (pintype "passive"))
      (node (ref "C40") (pin "2") (pinfunction "2_2") (pintype "passive"))
      (node (ref "C41") (pin "2") (pinfunction "2_2") (pintype "passive"))
      (node (ref "C42") (pin "2") (pinfunction "2_2") (pintype "passive"))
      (node (ref "C44") (pin "2") (pinfunction "2_2") (pintype "passive"))
      (node (ref "C45") (pin "2") (pinfunction "2_2") (pintype "passive"))
      (node (ref "C46") (pin "2") (pinfunction "2_2") (pintype "passive"))
      (node (ref "C48") (pin "2") (pinfunction "2_2") (pintype "passive"))
      (node (ref "C49") (pin "2") (pinfunction "2_2") (pintype "passive"))
      (node (ref "C5") (pin "2") (pinfunction "2_2") (pintype "passive"))
      (node (ref "C50") (pin "2") (pinfunction "2_2") (pintype "passive"))
      (node (ref "C51") (pin "2") (pinfunction "2_2") (pintype "passive"))
      (node (ref "C52") (pin "2") (pinfunction "2_2") (pintype "passive"))
      (node (ref "C53") (pin "2") (pinfunction "2_2") (pintype "passive"))
      (node (ref "C54") (pin "2") (pinfunction "2_2") (pintype "passive"))
      (node (ref "C55") (pin "2") (pinfunction "2_2") (pintype "passive"))
      (node (ref "C56") (pin "1") (pinfunction "1_1") (pintype "passive"))
      (node (ref "C57") (pin "1") (pinfunction "1_1") (pintype "passive"))
      (node (ref "C59") (pin "-") (pinfunction "-_-") (pintype "passive"))
      (node (ref "C6") (pin "1") (pinfunction "1_1") (pintype "passive"))
      (node (ref "C60") (pin "-") (pinfunction "-_-") (pintype "passive"))
      (node (ref "C62") (pin "2") (pinfunction "2_2") (pintype "passive"))
      (node (ref "C63") (pin "1") (pinfunction "1_1") (pintype "passive"))
      (node (ref "C64") (pin "1") (pinfunction "1_1") (pintype "passive"))
      (node (ref "C65") (pin "2") (pinfunction "2_2") (pintype "passive"))
      (node (ref "C68") (pin "-") (pinfunction "-_-") (pintype "passive"))
      (node (ref "C69") (pin "2") (pinfunction "2_2") (pintype "passive"))
      (node (ref "C7") (pin "1") (pinfunction "1_1") (pintype "passive"))
      (node (ref "C73") (pin "-") (pinfunction "-_-") (pintype "passive"))
      (node (ref "C74") (pin "1") (pinfunction "1_1") (pintype "passive"))
      (node (ref "C75") (pin "1") (pinfunction "1_1") (pintype "passive"))
      (node (ref "C8") (pin "1") (pinfunction "1_1") (pintype "passive"))
      (node (ref "CLK3") (pin "2") (pinfunction "S_2") (pintype "passive"))
      (node (ref "IC1") (pin "2") (pinfunction "GND_2") (pintype "bidirectional"))
      (node (ref "IC2") (pin "11") (pinfunction "V-_11") (pintype "power_in"))
      (node (ref "IC4") (pin "1") (pinfunction "1OE_1") (pintype "input"))
      (node (ref "IC4") (pin "15") (pinfunction "2OE_15") (pintype "input"))
      (node (ref "IC4") (pin "8") (pinfunction "VSS_8") (pintype "power_in"))
      (node (ref "IC5") (pin "18") (pinfunction "GND18_18") (pintype "power_in"))
      (node (ref "IC5") (pin "21") (pinfunction "GND21_21") (pintype "power_in"))
      (node (ref "IC5") (pin "25") (pinfunction "AGND_25") (pintype "power_in"))
      (node (ref "IC5") (pin "7") (pinfunction "GND7_7") (pintype "power_in"))
      (node (ref "IC6") (pin "7") (pinfunction "GND_7") (pintype "power_in"))
      (node (ref "IC7") (pin "8") (pinfunction "GND_8") (pintype "power_in"))
      (node (ref "IC8") (pin "21") (pinfunction "GND_21") (pintype "power_in"))
      (node (ref "IC8") (pin "3") (pinfunction "GND_3") (pintype "power_in"))
      (node (ref "IC8") (pin "5") (pinfunction "GND_5") (pintype "power_in"))
      (node (ref "JP1") (pin "6") (pinfunction "6_6") (pintype "passive"))
      (node (ref "JP2") (pin "1") (pinfunction "1_1") (pintype "passive"))
      (node (ref "K1") (pin "5") (pinfunction "5GND_5") (pintype "passive"))
      (node (ref "K1") (pin "Z1") (pinfunction "GND_Z1") (pintype "bidirectional"))
      (node (ref "K1") (pin "Z2") (pinfunction "GND_Z2") (pintype "bidirectional"))
      (node (ref "K1") (pin "Z3") (pinfunction "GND_Z3") (pintype "bidirectional"))
      (node (ref "K1") (pin "Z4") (pinfunction "GND_Z4") (pintype "bidirectional"))
      (node (ref "R11") (pin "1") (pinfunction "1_1") (pintype "passive"))
      (node (ref "R12") (pin "1") (pinfunction "1_1") (pintype "passive"))
      (node (ref "R18") (pin "1") (pinfunction "1_1") (pintype "passive"))
      (node (ref "R18") (pin "2") (pinfunction "2_2") (pintype "passive"))
      (node (ref "R23") (pin "1") (pinfunction "1_1") (pintype "passive"))
      (node (ref "R24") (pin "1") (pinfunction "1_1") (pintype "passive"))
      (node (ref "R32") (pin "1") (pinfunction "1_1") (pintype "passive"))
      (node (ref "S1") (pin "4") (pinfunction "P1_4") (pintype "passive"))
      (node (ref "T1") (pin "2") (pinfunction "S_2") (pintype "passive"))
      (node (ref "T2") (pin "2") (pinfunction "S_2") (pintype "passive"))
      (node (ref "T3") (pin "2") (pinfunction "S_2") (pintype "passive"))
      (node (ref "T4") (pin "2") (pinfunction "S_2") (pintype "passive"))
      (node (ref "T5") (pin "2") (pinfunction "S_2") (pintype "passive"))
      (node (ref "T6") (pin "2") (pinfunction "S_2") (pintype "passive"))
      (node (ref "T7") (pin "2") (pinfunction "S_2") (pintype "passive"))
      (node (ref "T8") (pin "2") (pinfunction "S_2") (pintype "passive"))
      (node (ref "U$21") (pin "PRIMARY_BOTTOM") (pinfunction "PRIM_BOTTOM_PRIMARY_BOTTOM") (pintype "bidirectional"))
      (node (ref "U$22") (pin "P$1") (pinfunction "2_P$1") (pintype "passive"))
      (node (ref "U$22") (pin "P$2") (pinfunction "2_P$2") (pintype "passive"))
      (node (ref "U$22") (pin "P$3") (pinfunction "2_P$3") (pintype "passive"))
      (node (ref "U$22") (pin "P$4") (pinfunction "2_P$4") (pintype "passive"))
      (node (ref "X1") (pin "S") (pinfunction "S_S") (pintype "passive"))
      (node (ref "X2") (pin "2") (pinfunction "S_2") (pintype "passive"))
    )
    (net (code "37") (name "I") (class "Default")
      (node (ref "C11") (pin "-") (pinfunction "-_-") (pintype "passive"))
      (node (ref "IC4") (pin "10") (pinfunction "2B1_10") (pintype "input"))
      (node (ref "IC4") (pin "6") (pinfunction "1B1_6") (pintype "input"))
    )
    (net (code "38") (name "I_IN") (class "Default")
      (node (ref "C3") (pin "-") (pinfunction "-_-") (pintype "passive"))
      (node (ref "X1") (pin "T") (pinfunction "T_T") (pintype "passive"))
    )
    (net (code "39") (name "LOAD") (class "Default")
      (node (ref "U$10") (pin "4") (pinfunction "OUT_4") (pintype "bidirectional"))
      (node (ref "U$11") (pin "4") (pinfunction "OUT_4") (pintype "bidirectional"))
      (node (ref "U$12") (pin "4") (pinfunction "OUT_4") (pintype "bidirectional"))
      (node (ref "U$13") (pin "4") (pinfunction "OUT_4") (pintype "bidirectional"))
      (node (ref "U$14") (pin "4") (pinfunction "OUT_4") (pintype "bidirectional"))
      (node (ref "U$15") (pin "4") (pinfunction "OUT_4") (pintype "bidirectional"))
      (node (ref "U$16") (pin "4") (pinfunction "OUT_4") (pintype "bidirectional"))
      (node (ref "U$22") (pin "MID") (pinfunction "1_MID") (pintype "passive"))
      (node (ref "U$9") (pin "4") (pinfunction "OUT_4") (pintype "bidirectional"))
    )
    (net (code "40") (name "Net-(C3-Pad+)") (class "Default")
      (node (ref "C3") (pin "+") (pinfunction "+_+") (pintype "passive"))
      (node (ref "R1") (pin "1") (pinfunction "1_1") (pintype "passive"))
    )
    (net (code "41") (name "Net-(C4-Pad2)") (class "Default")
      (node (ref "C4") (pin "2") (pinfunction "2_2") (pintype "passive"))
      (node (ref "JP2") (pin "2") (pinfunction "2_2") (pintype "passive"))
    )
    (net (code "42") (name "Net-(C7-Pad2)") (class "Default")
      (node (ref "C7") (pin "2") (pinfunction "2_2") (pintype "passive"))
      (node (ref "C9") (pin "+") (pinfunction "+_+") (pintype "passive"))
      (node (ref "R7") (pin "2") (pinfunction "2_2") (pintype "passive"))
    )
    (net (code "43") (name "Net-(C10-Pad+)") (class "Default")
      (node (ref "C10") (pin "+") (pinfunction "+_+") (pintype "passive"))
      (node (ref "C6") (pin "2") (pinfunction "2_2") (pintype "passive"))
      (node (ref "R9") (pin "2") (pinfunction "2_2") (pintype "passive"))
    )
    (net (code "44") (name "Net-(C11-Pad+)") (class "Default")
      (node (ref "C11") (pin "+") (pinfunction "+_+") (pintype "passive"))
      (node (ref "C8") (pin "2") (pinfunction "2_2") (pintype "passive"))
      (node (ref "R8") (pin "2") (pinfunction "2_2") (pintype "passive"))
    )
    (net (code "45") (name "Net-(C12-Pad+)") (class "Default")
      (node (ref "C12") (pin "+") (pinfunction "+_+") (pintype "passive"))
      (node (ref "C5") (pin "1") (pinfunction "1_1") (pintype "passive"))
      (node (ref "R10") (pin "2") (pinfunction "2_2") (pintype "passive"))
    )
    (net (code "46") (name "Net-(C56-Pad2)") (class "Default")
      (node (ref "C56") (pin "2") (pinfunction "2_2") (pintype "passive"))
      (node (ref "R22") (pin "1") (pinfunction "1_1") (pintype "passive"))
      (node (ref "R23") (pin "2") (pinfunction "2_2") (pintype "passive"))
      (node (ref "R28") (pin "1") (pinfunction "1_1") (pintype "passive"))
    )
    (net (code "47") (name "Net-(C57-Pad2)") (class "Default")
      (node (ref "C57") (pin "2") (pinfunction "2_2") (pintype "passive"))
      (node (ref "R17") (pin "1") (pinfunction "1_1") (pintype "passive"))
      (node (ref "R28") (pin "2") (pinfunction "2_2") (pintype "passive"))
    )
    (net (code "48") (name "Net-(C58-Pad+)") (class "Default")
      (node (ref "C58") (pin "+") (pinfunction "+_+") (pintype "passive"))
      (node (ref "R4") (pin "1") (pinfunction "1_1") (pintype "passive"))
    )
    (net (code "49") (name "Net-(C66-Pad1)") (class "Default")
      (node (ref "C66") (pin "1") (pinfunction "1_1") (pintype "passive"))
      (node (ref "R20") (pin "1") (pinfunction "1_1") (pintype "passive"))
      (node (ref "R30") (pin "1") (pinfunction "1_1") (pintype "passive"))
      (node (ref "U$18") (pin "B") (pinfunction "B_B") (pintype "passive"))
    )
    (net (code "50") (name "Net-(C67-Pad2)") (class "Default")
      (node (ref "C67") (pin "2") (pinfunction "2_2") (pintype "passive"))
      (node (ref "R21") (pin "1") (pinfunction "1_1") (pintype "passive"))
      (node (ref "R30") (pin "2") (pinfunction "2_2") (pintype "passive"))
      (node (ref "U$17") (pin "B") (pinfunction "B_B") (pintype "passive"))
    )
    (net (code "51") (name "Net-(C74-Pad2)") (class "Default")
      (node (ref "C74") (pin "2") (pinfunction "2_2") (pintype "passive"))
      (node (ref "R31") (pin "1") (pinfunction "1_1") (pintype "passive"))
      (node (ref "R32") (pin "2") (pinfunction "2_2") (pintype "passive"))
      (node (ref "R33") (pin "1") (pinfunction "1_1") (pintype "passive"))
    )
    (net (code "52") (name "Net-(CLK3A-S)") (class "Default")
      (node (ref "CLK3") (pin "1") (pinfunction "S_1") (pintype "passive"))
      (node (ref "IC7") (pin "6") (pinfunction "CLK2_6") (pintype "bidirectional"))
    )
    (net (code "53") (name "Net-(IC1-BYPASS)") (class "Default")
      (node (ref "C65") (pin "1") (pinfunction "1_1") (pintype "passive"))
      (node (ref "IC1") (pin "4") (pinfunction "BYPASS_4") (pintype "bidirectional"))
    )
    (net (code "54") (name "Net-(IC1-IN)") (class "Default")
      (node (ref "C60") (pin "+") (pinfunction "+_+") (pintype "passive"))
      (node (ref "IC1") (pin "1") (pinfunction "IN_1") (pintype "bidirectional"))
      (node (ref "IC1") (pin "3") (pinfunction "ON/OFF_3") (pintype "bidirectional"))
      (node (ref "L18") (pin "P$2") (pinfunction "2_P$2") (pintype "passive"))
    )
    (net (code "55") (name "Net-(IC2A--IN)") (class "Default")
      (node (ref "IC2") (pin "2") (pinfunction "-IN_2") (pintype "input"))
      (node (ref "R27") (pin "1") (pinfunction "1_1") (pintype "passive"))
      (node (ref "R6") (pin "2") (pinfunction "2_2") (pintype "passive"))
    )
    (net (code "56") (name "Net-(IC2A-OUT)") (class "Default")
      (node (ref "IC2") (pin "1") (pinfunction "OUT_1") (pintype "output"))
      (node (ref "R27") (pin "2") (pinfunction "2_2") (pintype "passive"))
      (node (ref "R8") (pin "1") (pinfunction "1_1") (pintype "passive"))
    )
    (net (code "57") (name "Net-(IC2B--IN)") (class "Default")
      (node (ref "IC2") (pin "6") (pinfunction "-IN_6") (pintype "input"))
      (node (ref "R1") (pin "2") (pinfunction "2_2") (pintype "passive"))
      (node (ref "R2") (pin "1") (pinfunction "1_1") (pintype "passive"))
    )
    (net (code "58") (name "Net-(IC2B-OUT)") (class "Default")
      (node (ref "IC2") (pin "7") (pinfunction "OUT_7") (pintype "output"))
      (node (ref "R10") (pin "1") (pinfunction "1_1") (pintype "passive"))
      (node (ref "R2") (pin "2") (pinfunction "2_2") (pintype "passive"))
      (node (ref "R6") (pin "1") (pinfunction "1_1") (pintype "passive"))
    )
    (net (code "59") (name "Net-(IC2C--IN)") (class "Default")
      (node (ref "IC2") (pin "9") (pinfunction "-IN_9") (pintype "input"))
      (node (ref "R3") (pin "1") (pinfunction "1_1") (pintype "passive"))
      (node (ref "R4") (pin "2") (pinfunction "2_2") (pintype "passive"))
    )
    (net (code "60") (name "Net-(IC2C-OUT)") (class "Default")
      (node (ref "IC2") (pin "8") (pinfunction "OUT_8") (pintype "output"))
      (node (ref "R3") (pin "2") (pinfunction "2_2") (pintype "passive"))
      (node (ref "R5") (pin "1") (pinfunction "1_1") (pintype "passive"))
      (node (ref "R9") (pin "1") (pinfunction "1_1") (pintype "passive"))
    )
    (net (code "61") (name "Net-(IC2D--IN)") (class "Default")
      (node (ref "IC2") (pin "13") (pinfunction "-IN_13") (pintype "input"))
      (node (ref "R26") (pin "1") (pinfunction "1_1") (pintype "passive"))
      (node (ref "R5") (pin "2") (pinfunction "2_2") (pintype "passive"))
    )
    (net (code "62") (name "Net-(IC2D-OUT)") (class "Default")
      (node (ref "IC2") (pin "14") (pinfunction "OUT_14") (pintype "output"))
      (node (ref "R26") (pin "2") (pinfunction "2_2") (pintype "passive"))
      (node (ref "R7") (pin "1") (pinfunction "1_1") (pintype "passive"))
    )
    (net (code "63") (name "Net-(IC2E-V+)") (class "Default")
      (node (ref "C64") (pin "2") (pinfunction "2_2") (pintype "passive"))
      (node (ref "IC2") (pin "4") (pinfunction "V+_4") (pintype "power_in"))
      (node (ref "JP3") (pin "2") (pinfunction "2_2") (pintype "passive"))
      (node (ref "R31") (pin "2") (pinfunction "2_2") (pintype "passive"))
    )
    (net (code "64") (name "Net-(IC4A-1A)") (class "Default")
      (node (ref "IC4") (pin "7") (pinfunction "1A_7") (pintype "tri_state"))
      (node (ref "R13") (pin "2") (pinfunction "2_2") (pintype "passive"))
    )
    (net (code "65") (name "Net-(IC4A-2A)") (class "Default")
      (node (ref "IC4") (pin "9") (pinfunction "2A_9") (pintype "tri_state"))
      (node (ref "R14") (pin "2") (pinfunction "2_2") (pintype "passive"))
    )
    (net (code "66") (name "Net-(IC6A-~{Q})") (class "Default")
      (node (ref "IC6") (pin "12") (pinfunction "D_12") (pintype "input"))
      (node (ref "IC6") (pin "6") (pinfunction "~{Q}_6") (pintype "output"))
    )
    (net (code "67") (name "Net-(IC7-CLK1)") (class "Default")
      (node (ref "IC7") (pin "9") (pinfunction "CLK1_9") (pintype "bidirectional"))
      (node (ref "X2") (pin "1") (pinfunction "S_1") (pintype "passive"))
    )
    (net (code "68") (name "Net-(IC7-XA)") (class "Default")
      (node (ref "IC7") (pin "2") (pinfunction "XA_2") (pintype "bidirectional"))
      (node (ref "Q2") (pin "2") (pinfunction "2_2") (pintype "passive"))
    )
    (net (code "69") (name "Net-(IC7-XB)") (class "Default")
      (node (ref "IC7") (pin "3") (pinfunction "XB_3") (pintype "bidirectional"))
      (node (ref "Q2") (pin "1") (pinfunction "1_1") (pintype "passive"))
    )
    (net (code "70") (name "Net-(IC8-AREF)") (class "Default")
      (node (ref "C54") (pin "1") (pinfunction "1_1") (pintype "passive"))
      (node (ref "IC8") (pin "20") (pinfunction "AREF_20") (pintype "passive"))
    )
    (net (code "71") (name "Net-(IC8-PB6(XTAL1{slash}TOSC1))") (class "Default")
      (node (ref "C51") (pin "1") (pinfunction "1_1") (pintype "passive"))
      (node (ref "IC8") (pin "7") (pinfunction "PB6(XTAL1/TOSC1)_7") (pintype "bidirectional"))
      (node (ref "Q1") (pin "2") (pinfunction "2_2") (pintype "passive"))
    )
    (net (code "72") (name "Net-(IC8-PB7(XTAL2{slash}TOSC2))") (class "Default")
      (node (ref "C50") (pin "1") (pinfunction "1_1") (pintype "passive"))
      (node (ref "IC8") (pin "8") (pinfunction "PB7(XTAL2/TOSC2)_8") (pintype "bidirectional"))
      (node (ref "Q1") (pin "1") (pinfunction "1_1") (pintype "passive"))
    )
    (net (code "73") (name "Net-(L1-2)") (class "Default")
      (node (ref "C15") (pin "1") (pinfunction "1_1") (pintype "passive"))
      (node (ref "C19") (pin "2") (pinfunction "2_2") (pintype "passive"))
      (node (ref "L1") (pin "P$2") (pinfunction "2_P$2") (pintype "passive"))
      (node (ref "L2") (pin "P$1") (pinfunction "1_P$1") (pintype "passive"))
    )
    (net (code "74") (name "Net-(L3-2)") (class "Default")
      (node (ref "C21") (pin "1") (pinfunction "1_1") (pintype "passive"))
      (node (ref "C23") (pin "2") (pinfunction "2_2") (pintype "passive"))
      (node (ref "L3") (pin "P$2") (pinfunction "2_P$2") (pintype "passive"))
      (node (ref "L4") (pin "P$1") (pinfunction "1_P$1") (pintype "passive"))
    )
    (net (code "75") (name "Net-(L5-2)") (class "Default")
      (node (ref "C33") (pin "1") (pinfunction "1_1") (pintype "passive"))
      (node (ref "C35") (pin "2") (pinfunction "2_2") (pintype "passive"))
      (node (ref "L5") (pin "P$2") (pinfunction "2_P$2") (pintype "passive"))
      (node (ref "L6") (pin "P$1") (pinfunction "1_P$1") (pintype "passive"))
    )
    (net (code "76") (name "Net-(L7-2)") (class "Default")
      (node (ref "C41") (pin "1") (pinfunction "1_1") (pintype "passive"))
      (node (ref "C43") (pin "2") (pinfunction "2_2") (pintype "passive"))
      (node (ref "L7") (pin "P$2") (pinfunction "2_P$2") (pintype "passive"))
      (node (ref "L8") (pin "P$1") (pinfunction "1_P$1") (pintype "passive"))
    )
    (net (code "77") (name "Net-(L10-1)") (class "Default")
      (node (ref "C25") (pin "1") (pinfunction "1_1") (pintype "passive"))
      (node (ref "C27") (pin "2") (pinfunction "2_2") (pintype "passive"))
      (node (ref "L10") (pin "P$1") (pinfunction "1_P$1") (pintype "passive"))
      (node (ref "L9") (pin "P$2") (pinfunction "2_P$2") (pintype "passive"))
    )
    (net (code "78") (name "Net-(L11-2)") (class "Default")
      (node (ref "C29") (pin "1") (pinfunction "1_1") (pintype "passive"))
      (node (ref "C31") (pin "2") (pinfunction "2_2") (pintype "passive"))
      (node (ref "L11") (pin "P$2") (pinfunction "2_P$2") (pintype "passive"))
      (node (ref "L12") (pin "P$1") (pinfunction "1_P$1") (pintype "passive"))
    )
    (net (code "79") (name "Net-(L13-2)") (class "Default")
      (node (ref "C37") (pin "1") (pinfunction "1_1") (pintype "passive"))
      (node (ref "C39") (pin "2") (pinfunction "2_2") (pintype "passive"))
      (node (ref "L13") (pin "P$2") (pinfunction "2_P$2") (pintype "passive"))
      (node (ref "L14") (pin "P$1") (pinfunction "1_P$1") (pintype "passive"))
    )
    (net (code "80") (name "Net-(L15-2)") (class "Default")
      (node (ref "C45") (pin "1") (pinfunction "1_1") (pintype "passive"))
      (node (ref "C47") (pin "2") (pinfunction "2_2") (pintype "passive"))
      (node (ref "L15") (pin "P$2") (pinfunction "2_P$2") (pintype "passive"))
      (node (ref "L16") (pin "P$1") (pinfunction "1_P$1") (pintype "passive"))
    )
    (net (code "81") (name "Net-(L17-1)") (class "Default")
      (node (ref "L17") (pin "P$1") (pinfunction "1_P$1") (pintype "passive"))
      (node (ref "U$20") (pin "SECONDARY2") (pinfunction "SEC_BOT_SECONDARY2") (pintype "bidirectional"))
    )
    (net (code "82") (name "Net-(L17-2)") (class "Default")
      (node (ref "L17") (pin "P$2") (pinfunction "2_P$2") (pintype "passive"))
      (node (ref "R21") (pin "2") (pinfunction "2_2") (pintype "passive"))
    )
    (net (code "83") (name "Net-(L21-1)") (class "Default")
      (node (ref "L21") (pin "P$1") (pinfunction "1_P$1") (pintype "passive"))
      (node (ref "U$20") (pin "SECONDARY1") (pinfunction "SEC_TOP_SECONDARY1") (pintype "bidirectional"))
    )
    (net (code "84") (name "Net-(L21-2)") (class "Default")
      (node (ref "L21") (pin "P$2") (pinfunction "2_P$2") (pintype "passive"))
      (node (ref "R20") (pin "2") (pinfunction "2_2") (pintype "passive"))
    )
    (net (code "85") (name "Net-(L22-1)") (class "Default")
      (node (ref "C1") (pin "1") (pinfunction "1_1") (pintype "passive"))
      (node (ref "L22") (pin "P$1") (pinfunction "1_P$1") (pintype "passive"))
      (node (ref "U$21") (pin "SECONDARY_MID") (pinfunction "SEC_MID_SECONDARY_MID") (pintype "bidirectional"))
    )
    (net (code "86") (name "Net-(R25-Pad1)") (class "Default")
      (node (ref "R25") (pin "1") (pinfunction "1_1") (pintype "passive"))
      (node (ref "U$19") (pin "B") (pinfunction "B_B") (pintype "passive"))
    )
    (net (code "87") (name "Net-(S1-S1)") (class "Default")
      (node (ref "R19") (pin "1") (pinfunction "1_1") (pintype "passive"))
      (node (ref "S1") (pin "2") (pinfunction "S1_2") (pintype "passive"))
    )
    (net (code "88") (name "Net-(T1-D)") (class "Default")
      (node (ref "D1") (pin "A") (pinfunction "A_A") (pintype "passive"))
      (node (ref "T1") (pin "1") (pinfunction "D_1") (pintype "passive"))
      (node (ref "U$1") (pin "3") (pinfunction "C-_3") (pintype "bidirectional"))
      (node (ref "U$9") (pin "2") (pinfunction "C+_2") (pintype "bidirectional"))
    )
    (net (code "89") (name "Net-(T2-D)") (class "Default")
      (node (ref "D2") (pin "A") (pinfunction "A_A") (pintype "passive"))
      (node (ref "T2") (pin "1") (pinfunction "D_1") (pintype "passive"))
      (node (ref "U$10") (pin "2") (pinfunction "C+_2") (pintype "bidirectional"))
      (node (ref "U$2") (pin "3") (pinfunction "C-_3") (pintype "bidirectional"))
    )
    (net (code "90") (name "Net-(T3-D)") (class "Default")
      (node (ref "D3") (pin "A") (pinfunction "A_A") (pintype "passive"))
      (node (ref "T3") (pin "1") (pinfunction "D_1") (pintype "passive"))
      (node (ref "U$11") (pin "2") (pinfunction "C+_2") (pintype "bidirectional"))
      (node (ref "U$3") (pin "3") (pinfunction "C-_3") (pintype "bidirectional"))
    )
    (net (code "91") (name "Net-(T4-D)") (class "Default")
      (node (ref "D4") (pin "A") (pinfunction "A_A") (pintype "passive"))
      (node (ref "T4") (pin "1") (pinfunction "D_1") (pintype "passive"))
      (node (ref "U$12") (pin "2") (pinfunction "C+_2") (pintype "bidirectional"))
      (node (ref "U$4") (pin "3") (pinfunction "C-_3") (pintype "bidirectional"))
    )
    (net (code "92") (name "Net-(T5-D)") (class "Default")
      (node (ref "D5") (pin "A") (pinfunction "A_A") (pintype "passive"))
      (node (ref "T5") (pin "1") (pinfunction "D_1") (pintype "passive"))
      (node (ref "U$13") (pin "2") (pinfunction "C+_2") (pintype "bidirectional"))
      (node (ref "U$5") (pin "3") (pinfunction "C-_3") (pintype "bidirectional"))
    )
    (net (code "93") (name "Net-(T6-D)") (class "Default")
      (node (ref "D6") (pin "A") (pinfunction "A_A") (pintype "passive"))
      (node (ref "T6") (pin "1") (pinfunction "D_1") (pintype "passive"))
      (node (ref "U$14") (pin "2") (pinfunction "C+_2") (pintype "bidirectional"))
      (node (ref "U$6") (pin "3") (pinfunction "C-_3") (pintype "bidirectional"))
    )
    (net (code "94") (name "Net-(T7-D)") (class "Default")
      (node (ref "D7") (pin "A") (pinfunction "A_A") (pintype "passive"))
      (node (ref "T7") (pin "1") (pinfunction "D_1") (pintype "passive"))
      (node (ref "U$15") (pin "2") (pinfunction "C+_2") (pintype "bidirectional"))
      (node (ref "U$7") (pin "3") (pinfunction "C-_3") (pintype "bidirectional"))
    )
    (net (code "95") (name "Net-(T8-D)") (class "Default")
      (node (ref "D8") (pin "A") (pinfunction "A_A") (pintype "passive"))
      (node (ref "T8") (pin "1") (pinfunction "D_1") (pintype "passive"))
      (node (ref "U$16") (pin "2") (pinfunction "C+_2") (pintype "bidirectional"))
      (node (ref "U$8") (pin "3") (pinfunction "C-_3") (pintype "bidirectional"))
    )
    (net (code "96") (name "Net-(U$17-C)") (class "Default")
      (node (ref "C66") (pin "2") (pinfunction "2_2") (pintype "passive"))
      (node (ref "C71") (pin "2") (pinfunction "2_2") (pintype "passive"))
      (node (ref "U$17") (pin "E") (pinfunction "C_E") (pintype "passive"))
    )
    (net (code "97") (name "Net-(U$17-E)") (class "Default")
      (node (ref "R11") (pin "2") (pinfunction "2_2") (pintype "passive"))
      (node (ref "U$17") (pin "C") (pinfunction "E_C") (pintype "passive"))
    )
    (net (code "98") (name "Net-(U$18-C)") (class "Default")
      (node (ref "C67") (pin "1") (pinfunction "1_1") (pintype "passive"))
      (node (ref "C70") (pin "1") (pinfunction "1_1") (pintype "passive"))
      (node (ref "U$18") (pin "E") (pinfunction "C_E") (pintype "passive"))
    )
    (net (code "99") (name "Net-(U$18-E)") (class "Default")
      (node (ref "R12") (pin "2") (pinfunction "2_2") (pintype "passive"))
      (node (ref "U$18") (pin "C") (pinfunction "E_C") (pintype "passive"))
    )
    (net (code "100") (name "Net-(U$19-C)") (class "Default")
      (node (ref "C2") (pin "1") (pinfunction "1_1") (pintype "passive"))
      (node (ref "R25") (pin "2") (pinfunction "2_2") (pintype "passive"))
      (node (ref "R29") (pin "2") (pinfunction "2_2") (pintype "passive"))
      (node (ref "U$19") (pin "E") (pinfunction "C_E") (pintype "passive"))
      (node (ref "U$20") (pin "SECONDARY_MID") (pinfunction "SEC_MID_SECONDARY_MID") (pintype "bidirectional"))
    )
    (net (code "101") (name "Net-(U$19-E)") (class "Default")
      (node (ref "R24") (pin "2") (pinfunction "2_2") (pintype "passive"))
      (node (ref "U$19") (pin "C") (pinfunction "E_C") (pintype "passive"))
    )
    (net (code "102") (name "Net-(U$21-SEC_BOT)") (class "Default")
      (node (ref "C70") (pin "2") (pinfunction "2_2") (pintype "passive"))
      (node (ref "U$21") (pin "SECONDARY2") (pinfunction "SEC_BOT_SECONDARY2") (pintype "bidirectional"))
    )
    (net (code "103") (name "Net-(U$21-SEC_TOP)") (class "Default")
      (node (ref "C71") (pin "1") (pinfunction "1_1") (pintype "passive"))
      (node (ref "U$21") (pin "SECONDARY1") (pinfunction "SEC_TOP_SECONDARY1") (pintype "bidirectional"))
    )
    (net (code "104") (name "OFFSET") (class "Default")
      (node (ref "C63") (pin "2") (pinfunction "2_2") (pintype "passive"))
      (node (ref "C68") (pin "+") (pinfunction "+_+") (pintype "passive"))
      (node (ref "R17") (pin "2") (pinfunction "2_2") (pintype "passive"))
      (node (ref "U$20") (pin "PRIMARY_BOTTOM") (pinfunction "PRIM_BOTTOM_PRIMARY_BOTTOM") (pintype "bidirectional"))
    )
    (net (code "105") (name "PA_IN") (class "Default")
      (node (ref "R13") (pin "1") (pinfunction "1_1") (pintype "passive"))
      (node (ref "R14") (pin "1") (pinfunction "1_1") (pintype "passive"))
      (node (ref "U$20") (pin "PRIMARY_TOP") (pinfunction "PRIM_TOP_PRIMARY_TOP") (pintype "bidirectional"))
    )
    (net (code "106") (name "PA_OUT") (class "Default")
      (node (ref "U$1") (pin "1") (pinfunction "IN_1") (pintype "bidirectional"))
      (node (ref "U$2") (pin "1") (pinfunction "IN_1") (pintype "bidirectional"))
      (node (ref "U$21") (pin "PRIMARY_TOP") (pinfunction "PRIM_TOP_PRIMARY_TOP") (pintype "bidirectional"))
      (node (ref "U$3") (pin "1") (pinfunction "IN_1") (pintype "bidirectional"))
      (node (ref "U$4") (pin "1") (pinfunction "IN_1") (pintype "bidirectional"))
      (node (ref "U$5") (pin "1") (pinfunction "IN_1") (pintype "bidirectional"))
      (node (ref "U$6") (pin "1") (pinfunction "IN_1") (pintype "bidirectional"))
      (node (ref "U$7") (pin "1") (pinfunction "IN_1") (pintype "bidirectional"))
      (node (ref "U$8") (pin "1") (pinfunction "IN_1") (pintype "bidirectional"))
    )
    (net (code "107") (name "PB3") (class "Default")
      (node (ref "IC8") (pin "15") (pinfunction "PB3(MOSI/OC2)_15") (pintype "bidirectional"))
      (node (ref "JP1") (pin "4") (pinfunction "4_4") (pintype "passive"))
    )
    (net (code "108") (name "PB4") (class "Default")
      (node (ref "IC8") (pin "16") (pinfunction "PB4(MISO)_16") (pintype "bidirectional"))
      (node (ref "JP1") (pin "1") (pinfunction "1_1") (pintype "passive"))
    )
    (net (code "109") (name "PB5") (class "Default")
      (node (ref "IC8") (pin "17") (pinfunction "PB5(SCK)_17") (pintype "bidirectional"))
      (node (ref "JP1") (pin "3") (pinfunction "3_3") (pintype "passive"))
    )
    (net (code "110") (name "Q") (class "Default")
      (node (ref "C9") (pin "-") (pinfunction "-_-") (pintype "passive"))
      (node (ref "IC4") (pin "11") (pinfunction "2B2_11") (pintype "input"))
      (node (ref "IC4") (pin "5") (pinfunction "1B2_5") (pintype "input"))
    )
    (net (code "111") (name "Q_IN") (class "Default")
      (node (ref "C58") (pin "-") (pinfunction "-_-") (pintype "passive"))
      (node (ref "X1") (pin "R") (pinfunction "R_R") (pintype "passive"))
    )
    (net (code "112") (name "RESET") (class "Default")
      (node (ref "C4") (pin "1") (pinfunction "1_1") (pintype "passive"))
      (node (ref "IC8") (pin "29") (pinfunction "PC6(/RESET)_29") (pintype "bidirectional"))
      (node (ref "JP1") (pin "5") (pinfunction "5_5") (pintype "passive"))
      (node (ref "R19") (pin "2") (pinfunction "2_2") (pintype "passive"))
    )
    (net (code "113") (name "RX") (class "Default")
      (node (ref "IC5") (pin "5") (pinfunction "RXD_5") (pintype "input"))
      (node (ref "IC8") (pin "30") (pinfunction "PD0(RXD)_30") (pintype "bidirectional"))
    )
    (net (code "114") (name "SCL") (class "Default")
      (node (ref "IC7") (pin "4") (pinfunction "SCL_4") (pintype "bidirectional"))
      (node (ref "IC8") (pin "28") (pinfunction "PC5(ADC5/SCL)_28") (pintype "bidirectional"))
      (node (ref "R16") (pin "1") (pinfunction "1_1") (pintype "passive"))
    )
    (net (code "115") (name "SDA") (class "Default")
      (node (ref "IC7") (pin "5") (pinfunction "SDA_5") (pintype "bidirectional"))
      (node (ref "IC8") (pin "27") (pinfunction "PC4(ADC4/SDA)_27") (pintype "bidirectional"))
      (node (ref "R15") (pin "1") (pinfunction "1_1") (pintype "passive"))
    )
    (net (code "116") (name "SI4F") (class "Default")
      (node (ref "IC6") (pin "11") (pinfunction "CLK_11") (pintype "input"))
      (node (ref "IC6") (pin "3") (pinfunction "CLK_3") (pintype "input"))
      (node (ref "IC7") (pin "10") (pinfunction "CLK0_10") (pintype "bidirectional"))
    )
    (net (code "117") (name "TX") (class "Default")
      (node (ref "IC5") (pin "1") (pinfunction "TXD_1") (pintype "output"))
      (node (ref "IC8") (pin "31") (pinfunction "PD1(TXD)_31") (pintype "bidirectional"))
    )
    (net (code "118") (name "UC_VCC") (class "Default")
      (node (ref "C52") (pin "1") (pinfunction "1_1") (pintype "passive"))
      (node (ref "C53") (pin "1") (pinfunction "1_1") (pintype "passive"))
      (node (ref "IC5") (pin "17") (pinfunction "3V3OUT_17") (pintype "output"))
      (node (ref "IC8") (pin "18") (pinfunction "AVCC_18") (pintype "power_in"))
      (node (ref "IC8") (pin "4") (pinfunction "VCC_4") (pintype "power_in"))
      (node (ref "IC8") (pin "6") (pinfunction "VCC_6") (pintype "power_in"))
      (node (ref "JP1") (pin "2") (pinfunction "2_2") (pintype "passive"))
    )
    (net (code "119") (name "unconnected-(IC5-CTS-Pad11)") (class "Default")
      (node (ref "IC5") (pin "11") (pinfunction "CTS_11") (pintype "input"))
    )
    (net (code "120") (name "unconnected-(IC5-DCD-Pad10)") (class "Default")
      (node (ref "IC5") (pin "10") (pinfunction "DCD_10") (pintype "input"))
    )
    (net (code "121") (name "unconnected-(IC5-DSR-Pad9)") (class "Default")
      (node (ref "IC5") (pin "9") (pinfunction "DSR_9") (pintype "input"))
    )
    (net (code "122") (name "unconnected-(IC5-OSCI-Pad27)") (class "Default")
      (node (ref "IC5") (pin "27") (pinfunction "OSCI_27") (pintype "input"))
    )
    (net (code "123") (name "unconnected-(IC5-OSCO-Pad28)") (class "Default")
      (node (ref "IC5") (pin "28") (pinfunction "OSCO_28") (pintype "output"))
    )
    (net (code "124") (name "unconnected-(IC5-PWREN{slash}CBUS3-Pad14)") (class "Default")
      (node (ref "IC5") (pin "14") (pinfunction "PWREN/CBUS3_14") (pintype "input"))
    )
    (net (code "125") (name "unconnected-(IC5-RESET-Pad19)") (class "Default")
      (node (ref "IC5") (pin "19") (pinfunction "RESET_19") (pintype "input"))
    )
    (net (code "126") (name "unconnected-(IC5-RI-Pad6)") (class "Default")
      (node (ref "IC5") (pin "6") (pinfunction "RI_6") (pintype "input"))
    )
    (net (code "127") (name "unconnected-(IC5-RTS-Pad3)") (class "Default")
      (node (ref "IC5") (pin "3") (pinfunction "RTS_3") (pintype "output"))
    )
    (net (code "128") (name "unconnected-(IC5-RXLED{slash}CBUS1-Pad22)") (class "Default")
      (node (ref "IC5") (pin "22") (pinfunction "RXLED/CBUS1_22") (pintype "input"))
    )
    (net (code "129") (name "unconnected-(IC5-SLEEP{slash}CBUS4-Pad12)") (class "Default")
      (node (ref "IC5") (pin "12") (pinfunction "SLEEP/CBUS4_12") (pintype "input"))
    )
    (net (code "130") (name "unconnected-(IC5-TEST-Pad26)") (class "Default")
      (node (ref "IC5") (pin "26") (pinfunction "TEST_26") (pintype "input"))
    )
    (net (code "131") (name "unconnected-(IC5-TXDEN{slash}CBUS2-Pad13)") (class "Default")
      (node (ref "IC5") (pin "13") (pinfunction "TXDEN/CBUS2_13") (pintype "input"))
    )
    (net (code "132") (name "unconnected-(IC5-TXLED{slash}CBUS0-Pad23)") (class "Default")
      (node (ref "IC5") (pin "23") (pinfunction "TXLED/CBUS0_23") (pintype "input"))
    )
    (net (code "133") (name "unconnected-(IC6B-~{Q}-Pad8)") (class "Default")
      (node (ref "IC6") (pin "8") (pinfunction "~{Q}_8") (pintype "output"))
    )
    (net (code "134") (name "unconnected-(IC8-ADC6-Pad19)") (class "Default")
      (node (ref "IC8") (pin "19") (pinfunction "ADC6_19") (pintype "bidirectional"))
    )
    (net (code "135") (name "unconnected-(IC8-ADC7-Pad22)") (class "Default")
      (node (ref "IC8") (pin "22") (pinfunction "ADC7_22") (pintype "bidirectional"))
    )
    (net (code "136") (name "unconnected-(IC8-PB2(SS{slash}OC1B)-Pad14)") (class "Default")
      (node (ref "IC8") (pin "14") (pinfunction "PB2(SS/OC1B)_14") (pintype "bidirectional"))
    )
    (net (code "137") (name "unconnected-(IC8-PC0(ADC0)-Pad23)") (class "Default")
      (node (ref "IC8") (pin "23") (pinfunction "PC0(ADC0)_23") (pintype "bidirectional"))
    )
    (net (code "138") (name "unconnected-(IC8-PC1(ADC1)-Pad24)") (class "Default")
      (node (ref "IC8") (pin "24") (pinfunction "PC1(ADC1)_24") (pintype "bidirectional"))
    )
    (net (code "139") (name "unconnected-(IC8-PC2(ADC2)-Pad25)") (class "Default")
      (node (ref "IC8") (pin "25") (pinfunction "PC2(ADC2)_25") (pintype "bidirectional"))
    )
    (net (code "140") (name "unconnected-(IC8-PC3(ADC3)-Pad26)") (class "Default")
      (node (ref "IC8") (pin "26") (pinfunction "PC3(ADC3)_26") (pintype "bidirectional"))
    )
    (net (code "141") (name "unconnected-(K1-4ID-Pad4)") (class "Default")
      (node (ref "K1") (pin "4") (pinfunction "4ID_4") (pintype "passive"))
    )
    (net (code "142") (name "unconnected-(S1-P-Pad3)") (class "Default")
      (node (ref "S1") (pin "3") (pinfunction "P_3") (pintype "passive"))
    )
    (net (code "143") (name "unconnected-(S1-S-Pad1)") (class "Default")
      (node (ref "S1") (pin "1") (pinfunction "S_1") (pintype "passive"))
    )
    (net (code "144") (name "unconnected-(X1-PadB)") (class "Default")
      (node (ref "X1") (pin "B") (pinfunction "B_B") (pintype "passive"))
    )
  )
)
